# LED_Cube.net
KiCad netlist of a schematic drawn in EAGLE
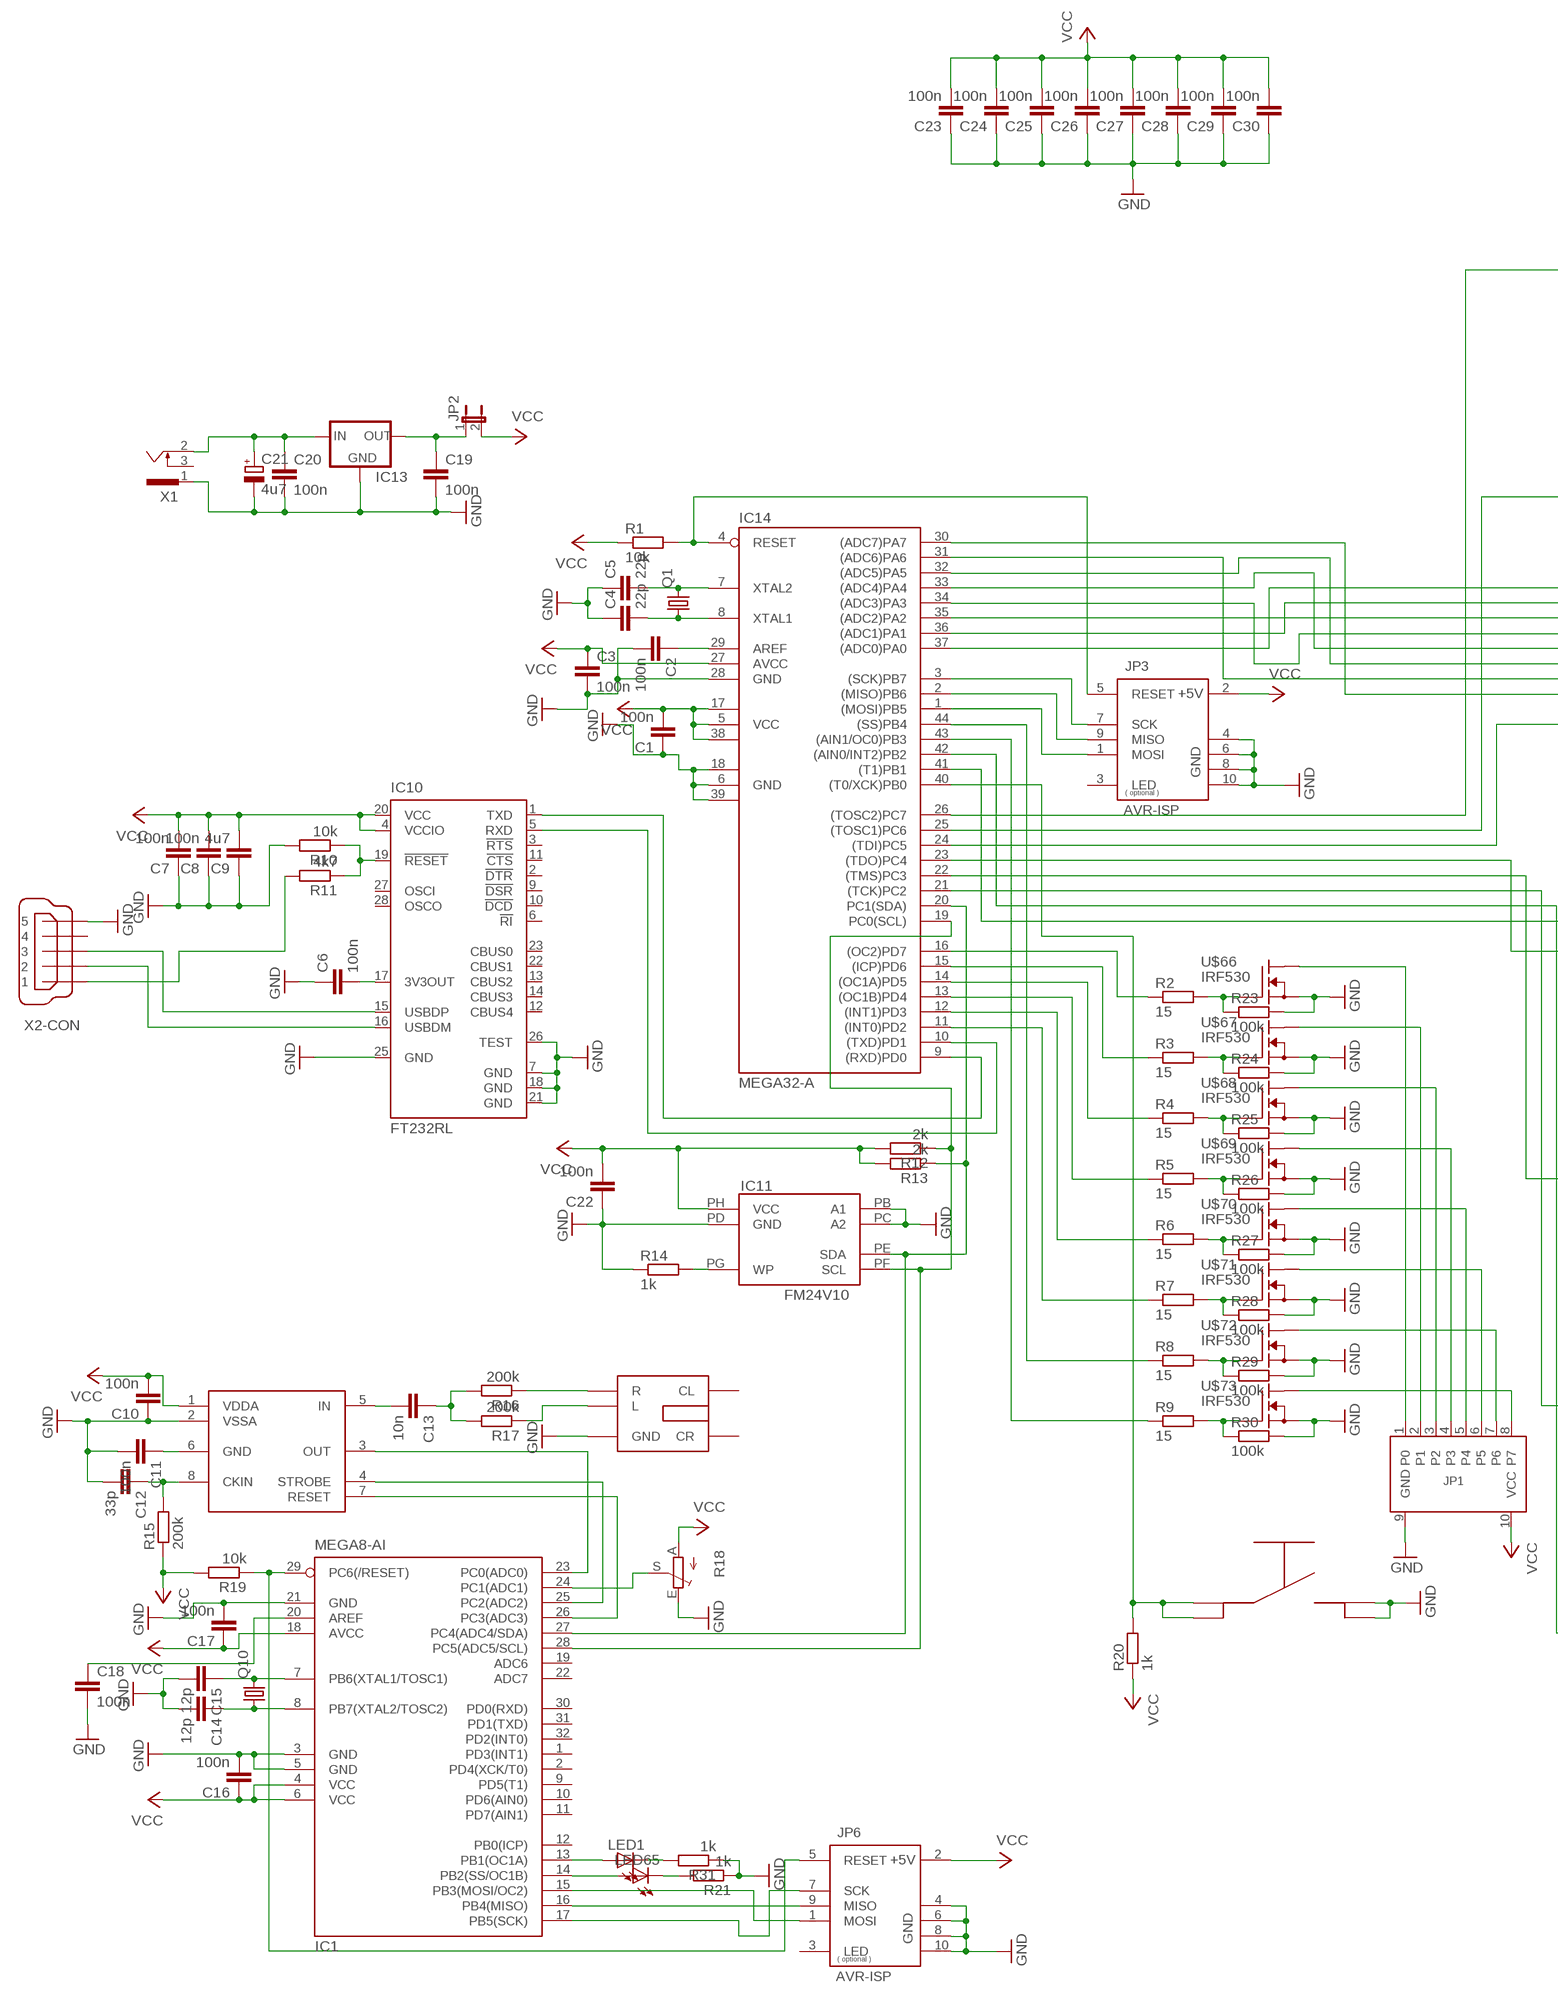
[diagram p0: schematic, sheet 1, part 1 of 2]
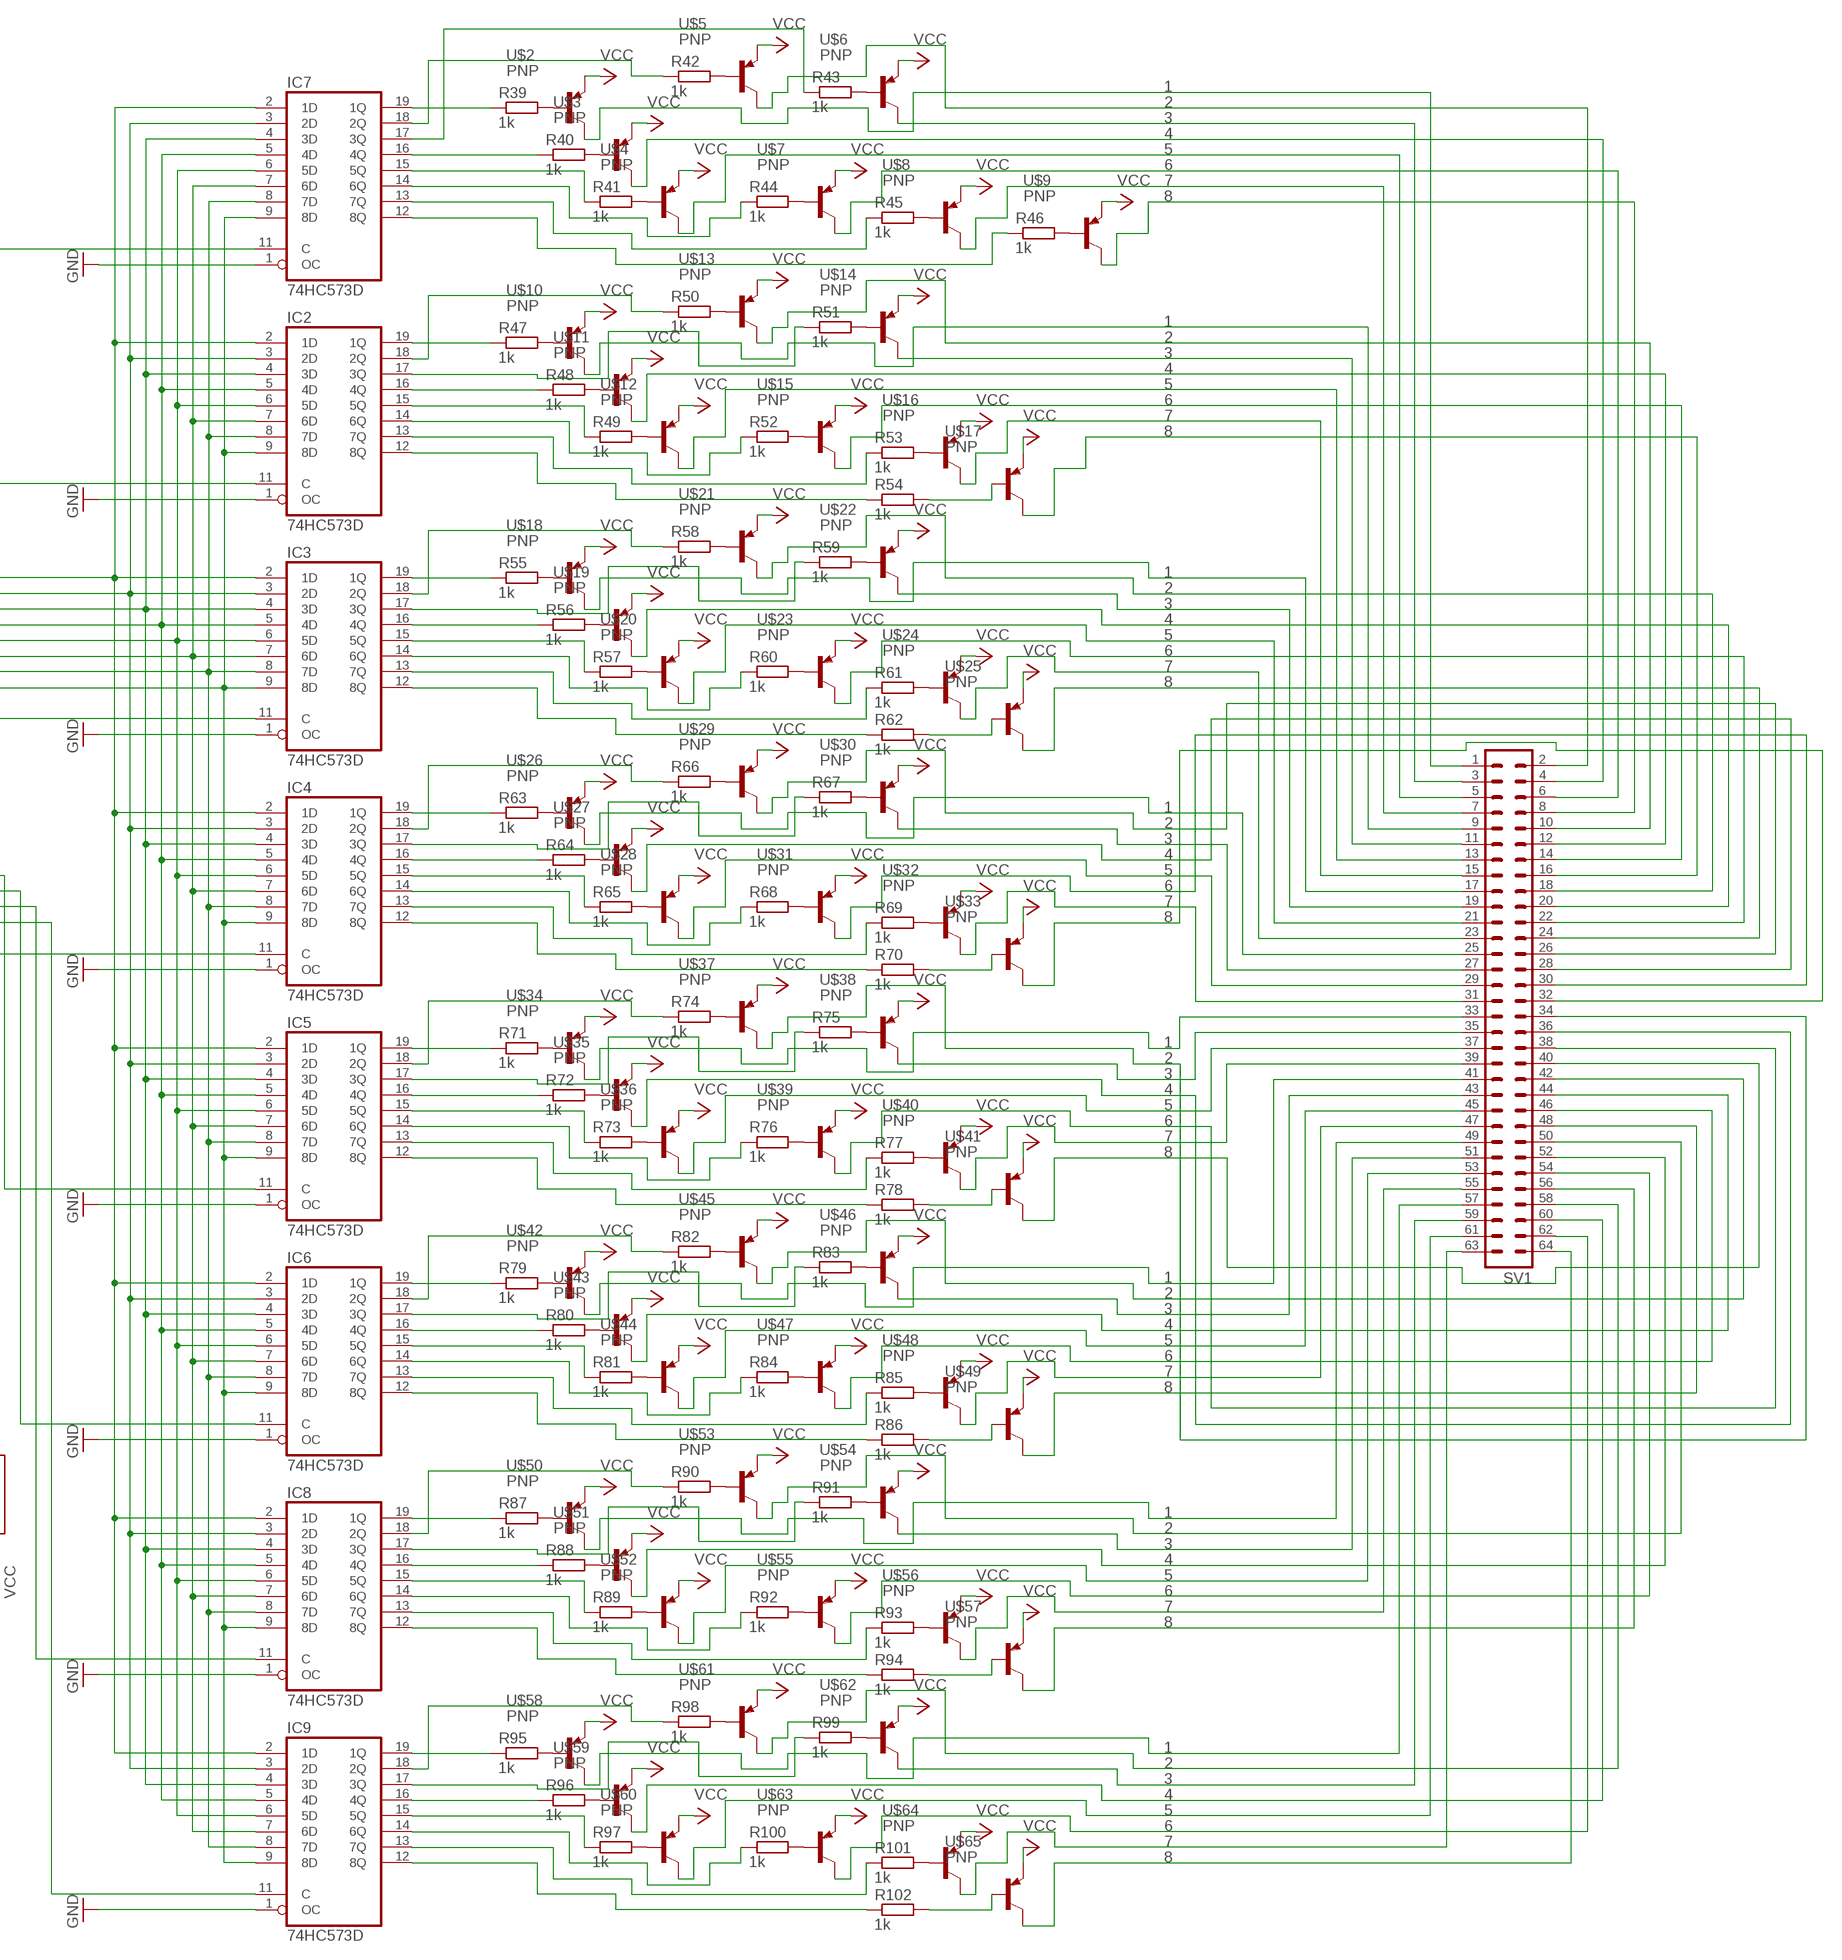
[diagram p1: schematic, sheet 1, part 2 of 2]

(export (version "E")
  (design (tool "Eeschema 10.0.6"))
  (components
    (comp (ref "C1")
      (value "100n")
      (footprint "eagle-import:C0603")
      (libsource (lib "eagle-import") (part "C-EUC0603"))
    )
    (comp (ref "C2")
      (value "100n")
      (footprint "eagle-import:C0603")
      (libsource (lib "eagle-import") (part "C-EUC0603"))
    )
    (comp (ref "C3")
      (value "100n")
      (footprint "eagle-import:C0603")
      (libsource (lib "eagle-import") (part "C-EUC0603"))
    )
    (comp (ref "C4")
      (value "22p")
      (footprint "eagle-import:C0603")
      (libsource (lib "eagle-import") (part "C-EUC0603"))
    )
    (comp (ref "C5")
      (value "22p")
      (footprint "eagle-import:C0603")
      (libsource (lib "eagle-import") (part "C-EUC0603"))
    )
    (comp (ref "C6")
      (value "100n")
      (footprint "eagle-import:C0603")
      (libsource (lib "eagle-import") (part "C-EUC0603"))
    )
    (comp (ref "C7")
      (value "100n")
      (footprint "eagle-import:C0603")
      (libsource (lib "eagle-import") (part "C-EUC0603"))
    )
    (comp (ref "C8")
      (value "100n")
      (footprint "eagle-import:C0603")
      (libsource (lib "eagle-import") (part "C-EUC0603"))
    )
    (comp (ref "C9")
      (value "4u7")
      (footprint "eagle-import:C0603")
      (libsource (lib "eagle-import") (part "C-EUC0603"))
    )
    (comp (ref "C10")
      (value "100n")
      (footprint "eagle-import:C0603")
      (libsource (lib "eagle-import") (part "C-EUC0603"))
    )
    (comp (ref "C11")
      (value "100n")
      (footprint "eagle-import:C0603")
      (libsource (lib "eagle-import") (part "C-EUC0603"))
    )
    (comp (ref "C12")
      (value "33p")
      (footprint "eagle-import:C0603")
      (libsource (lib "eagle-import") (part "C-EUC0603"))
    )
    (comp (ref "C13")
      (value "10n")
      (footprint "eagle-import:C0603")
      (libsource (lib "eagle-import") (part "C-EUC0603"))
    )
    (comp (ref "C14")
      (value "12p")
      (footprint "eagle-import:C0603")
      (libsource (lib "eagle-import") (part "C-EUC0603"))
    )
    (comp (ref "C15")
      (value "12p")
      (footprint "eagle-import:C0603")
      (libsource (lib "eagle-import") (part "C-EUC0603"))
    )
    (comp (ref "C16")
      (value "100n")
      (footprint "eagle-import:C0603")
      (libsource (lib "eagle-import") (part "C-EUC0603"))
    )
    (comp (ref "C17")
      (value "100n")
      (footprint "eagle-import:C0603")
      (libsource (lib "eagle-import") (part "C-EUC0603"))
    )
    (comp (ref "C18")
      (value "100n")
      (footprint "eagle-import:C0603")
      (libsource (lib "eagle-import") (part "C-EUC0603"))
    )
    (comp (ref "C19")
      (value "100n")
      (footprint "eagle-import:C0603")
      (libsource (lib "eagle-import") (part "C-EUC0603"))
    )
    (comp (ref "C20")
      (value "100n")
      (footprint "eagle-import:C0603")
      (libsource (lib "eagle-import") (part "C-EUC0603"))
    )
    (comp (ref "C21")
      (value "4u7")
      (footprint "eagle-import:TAP5-80")
      (libsource (lib "eagle-import") (part "CPOL-EUTAP5-80"))
    )
    (comp (ref "C22")
      (value "100n")
      (footprint "eagle-import:C0603")
      (libsource (lib "eagle-import") (part "C-EUC0603"))
    )
    (comp (ref "C23")
      (value "100n")
      (footprint "eagle-import:C0603")
      (libsource (lib "eagle-import") (part "C-EUC0603"))
    )
    (comp (ref "C24")
      (value "100n")
      (footprint "eagle-import:C0603")
      (libsource (lib "eagle-import") (part "C-EUC0603"))
    )
    (comp (ref "C25")
      (value "100n")
      (footprint "eagle-import:C0603")
      (libsource (lib "eagle-import") (part "C-EUC0603"))
    )
    (comp (ref "C26")
      (value "100n")
      (footprint "eagle-import:C0603")
      (libsource (lib "eagle-import") (part "C-EUC0603"))
    )
    (comp (ref "C27")
      (value "100n")
      (footprint "eagle-import:C0603")
      (libsource (lib "eagle-import") (part "C-EUC0603"))
    )
    (comp (ref "C28")
      (value "100n")
      (footprint "eagle-import:C0603")
      (libsource (lib "eagle-import") (part "C-EUC0603"))
    )
    (comp (ref "C29")
      (value "100n")
      (footprint "eagle-import:C0603")
      (libsource (lib "eagle-import") (part "C-EUC0603"))
    )
    (comp (ref "C30")
      (value "100n")
      (footprint "eagle-import:C0603")
      (libsource (lib "eagle-import") (part "C-EUC0603"))
    )
    (comp (ref "IC1")
      (value "MEGA8-AI")
      (footprint "eagle-import:TQFP32-08")
      (fields (field (name "MPN") "ATMEGA8-16AU"))
      (libsource (lib "eagle-import") (part "MEGA8-AI"))
    )
    (comp (ref "IC2")
      (value "74HC573D")
      (footprint "eagle-import:SO20W")
      (libsource (lib "eagle-import") (part "74573DHC"))
    )
    (comp (ref "IC3")
      (value "74HC573D")
      (footprint "eagle-import:SO20W")
      (libsource (lib "eagle-import") (part "74573DHC"))
    )
    (comp (ref "IC4")
      (value "74HC573D")
      (footprint "eagle-import:SO20W")
      (libsource (lib "eagle-import") (part "74573DHC"))
    )
    (comp (ref "IC5")
      (value "74HC573D")
      (footprint "eagle-import:SO20W")
      (libsource (lib "eagle-import") (part "74573DHC"))
    )
    (comp (ref "IC6")
      (value "74HC573D")
      (footprint "eagle-import:SO20W")
      (libsource (lib "eagle-import") (part "74573DHC"))
    )
    (comp (ref "IC7")
      (value "74HC573D")
      (footprint "eagle-import:SO20W")
      (libsource (lib "eagle-import") (part "74573DHC"))
    )
    (comp (ref "IC8")
      (value "74HC573D")
      (footprint "eagle-import:SO20W")
      (libsource (lib "eagle-import") (part "74573DHC"))
    )
    (comp (ref "IC9")
      (value "74HC573D")
      (footprint "eagle-import:SO20W")
      (libsource (lib "eagle-import") (part "74573DHC"))
    )
    (comp (ref "IC10")
      (value "FT232RL")
      (footprint "eagle-import:SSOP28")
      (libsource (lib "eagle-import") (part "FT232RL"))
    )
    (comp (ref "IC11")
      (value "FM24V10")
      (footprint "eagle-import:SOIC8")
      (libsource (lib "eagle-import") (part "FM24V10"))
    )
    (comp (ref "IC12")
      (value "MSGEQ7")
      (footprint "eagle-import:DIP8")
      (libsource (lib "eagle-import") (part "MSGEQ7"))
    )
    (comp (ref "IC13")
      (value "78XXS")
      (footprint "eagle-import:78XXS")
      (libsource (lib "eagle-import") (part "78XXS"))
    )
    (comp (ref "IC14")
      (value "MEGA32-A")
      (footprint "eagle-import:TQFP44")
      (fields (field (name "MPN") "ATMEGA32-16AU"))
      (libsource (lib "eagle-import") (part "MEGA32-A"))
    )
    (comp (ref "JP1")
      (value "PORT")
      (footprint "eagle-import:ML10")
      (libsource (lib "eagle-import") (part "PORT"))
    )
    (comp (ref "JP2")
      (value "JP1E")
      (footprint "eagle-import:JP1")
      (libsource (lib "eagle-import") (part "JP1E"))
    )
    (comp (ref "JP3")
      (value "AVR-ISP")
      (footprint "eagle-import:ML10")
      (libsource (lib "eagle-import") (part "AVR-ISP"))
    )
    (comp (ref "JP6")
      (value "AVR-ISP")
      (footprint "eagle-import:ML10")
      (libsource (lib "eagle-import") (part "AVR-ISP"))
    )
    (comp (ref "LED1")
      (value "LEDCHIPLED_0603")
      (footprint "eagle-import:CHIPLED_0603")
      (libsource (lib "eagle-import") (part "LEDCHIPLED_0603"))
    )
    (comp (ref "LED65")
      (value "LEDCHIPLED_0603")
      (footprint "eagle-import:CHIPLED_0603")
      (libsource (lib "eagle-import") (part "LEDCHIPLED_0603"))
    )
    (comp (ref "Q1")
      (value "CRYSTALHC49S")
      (footprint "eagle-import:HC49_S")
      (libsource (lib "eagle-import") (part "CRYSTALHC49S"))
    )
    (comp (ref "Q10")
      (value "CRYSTALHC49S")
      (footprint "eagle-import:HC49_S")
      (libsource (lib "eagle-import") (part "CRYSTALHC49S"))
    )
    (comp (ref "R1")
      (value "10k")
      (footprint "eagle-import:R0603")
      (libsource (lib "eagle-import") (part "R-EU_R0603"))
    )
    (comp (ref "R2")
      (value "15")
      (footprint "eagle-import:R0603")
      (libsource (lib "eagle-import") (part "R-EU_R0603"))
    )
    (comp (ref "R3")
      (value "15")
      (footprint "eagle-import:R0603")
      (libsource (lib "eagle-import") (part "R-EU_R0603"))
    )
    (comp (ref "R4")
      (value "15")
      (footprint "eagle-import:R0603")
      (libsource (lib "eagle-import") (part "R-EU_R0603"))
    )
    (comp (ref "R5")
      (value "15")
      (footprint "eagle-import:R0603")
      (libsource (lib "eagle-import") (part "R-EU_R0603"))
    )
    (comp (ref "R6")
      (value "15")
      (footprint "eagle-import:R0603")
      (libsource (lib "eagle-import") (part "R-EU_R0603"))
    )
    (comp (ref "R7")
      (value "15")
      (footprint "eagle-import:R0603")
      (libsource (lib "eagle-import") (part "R-EU_R0603"))
    )
    (comp (ref "R8")
      (value "15")
      (footprint "eagle-import:R0603")
      (libsource (lib "eagle-import") (part "R-EU_R0603"))
    )
    (comp (ref "R9")
      (value "15")
      (footprint "eagle-import:R0603")
      (libsource (lib "eagle-import") (part "R-EU_R0603"))
    )
    (comp (ref "R10")
      (value "10k")
      (footprint "eagle-import:R0603")
      (libsource (lib "eagle-import") (part "R-EU_R0603"))
    )
    (comp (ref "R11")
      (value "4k7")
      (footprint "eagle-import:R0603")
      (libsource (lib "eagle-import") (part "R-EU_R0603"))
    )
    (comp (ref "R12")
      (value "2k")
      (footprint "eagle-import:R0603")
      (libsource (lib "eagle-import") (part "R-EU_R0603"))
    )
    (comp (ref "R13")
      (value "2k")
      (footprint "eagle-import:R0603")
      (libsource (lib "eagle-import") (part "R-EU_R0603"))
    )
    (comp (ref "R14")
      (value "1k")
      (footprint "eagle-import:R0603")
      (libsource (lib "eagle-import") (part "R-EU_R0603"))
    )
    (comp (ref "R15")
      (value "200k")
      (footprint "eagle-import:R0603")
      (libsource (lib "eagle-import") (part "R-EU_R0603"))
    )
    (comp (ref "R16")
      (value "200k")
      (footprint "eagle-import:R0603")
      (libsource (lib "eagle-import") (part "R-EU_R0603"))
    )
    (comp (ref "R17")
      (value "200k")
      (footprint "eagle-import:R0603")
      (libsource (lib "eagle-import") (part "R-EU_R0603"))
    )
    (comp (ref "R18")
      (value "TRIM_EU-PT10S")
      (footprint "eagle-import:PT-10S")
      (libsource (lib "eagle-import") (part "TRIM_EU-PT10S"))
    )
    (comp (ref "R19")
      (value "10k")
      (footprint "eagle-import:R0603")
      (libsource (lib "eagle-import") (part "R-EU_R0603"))
    )
    (comp (ref "R20")
      (value "1k")
      (footprint "eagle-import:R0603")
      (libsource (lib "eagle-import") (part "R-EU_R0603"))
    )
    (comp (ref "R21")
      (value "1k")
      (footprint "eagle-import:R0603")
      (libsource (lib "eagle-import") (part "R-EU_R0603"))
    )
    (comp (ref "R23")
      (value "100k")
      (footprint "eagle-import:R0603")
      (libsource (lib "eagle-import") (part "R-EU_R0603"))
    )
    (comp (ref "R24")
      (value "100k")
      (footprint "eagle-import:R0603")
      (libsource (lib "eagle-import") (part "R-EU_R0603"))
    )
    (comp (ref "R25")
      (value "100k")
      (footprint "eagle-import:R0603")
      (libsource (lib "eagle-import") (part "R-EU_R0603"))
    )
    (comp (ref "R26")
      (value "100k")
      (footprint "eagle-import:R0603")
      (libsource (lib "eagle-import") (part "R-EU_R0603"))
    )
    (comp (ref "R27")
      (value "100k")
      (footprint "eagle-import:R0603")
      (libsource (lib "eagle-import") (part "R-EU_R0603"))
    )
    (comp (ref "R28")
      (value "100k")
      (footprint "eagle-import:R0603")
      (libsource (lib "eagle-import") (part "R-EU_R0603"))
    )
    (comp (ref "R29")
      (value "100k")
      (footprint "eagle-import:R0603")
      (libsource (lib "eagle-import") (part "R-EU_R0603"))
    )
    (comp (ref "R30")
      (value "100k")
      (footprint "eagle-import:R0603")
      (libsource (lib "eagle-import") (part "R-EU_R0603"))
    )
    (comp (ref "R31")
      (value "1k")
      (footprint "eagle-import:R0603")
      (libsource (lib "eagle-import") (part "R-EU_R0603"))
    )
    (comp (ref "R39")
      (value "1k")
      (footprint "eagle-import:R0603")
      (libsource (lib "eagle-import") (part "R-EU_R0603"))
    )
    (comp (ref "R40")
      (value "1k")
      (footprint "eagle-import:R0603")
      (libsource (lib "eagle-import") (part "R-EU_R0603"))
    )
    (comp (ref "R41")
      (value "1k")
      (footprint "eagle-import:R0603")
      (libsource (lib "eagle-import") (part "R-EU_R0603"))
    )
    (comp (ref "R42")
      (value "1k")
      (footprint "eagle-import:R0603")
      (libsource (lib "eagle-import") (part "R-EU_R0603"))
    )
    (comp (ref "R43")
      (value "1k")
      (footprint "eagle-import:R0603")
      (libsource (lib "eagle-import") (part "R-EU_R0603"))
    )
    (comp (ref "R44")
      (value "1k")
      (footprint "eagle-import:R0603")
      (libsource (lib "eagle-import") (part "R-EU_R0603"))
    )
    (comp (ref "R45")
      (value "1k")
      (footprint "eagle-import:R0603")
      (libsource (lib "eagle-import") (part "R-EU_R0603"))
    )
    (comp (ref "R46")
      (value "1k")
      (footprint "eagle-import:R0603")
      (libsource (lib "eagle-import") (part "R-EU_R0603"))
    )
    (comp (ref "R47")
      (value "1k")
      (footprint "eagle-import:R0603")
      (libsource (lib "eagle-import") (part "R-EU_R0603"))
    )
    (comp (ref "R48")
      (value "1k")
      (footprint "eagle-import:R0603")
      (libsource (lib "eagle-import") (part "R-EU_R0603"))
    )
    (comp (ref "R49")
      (value "1k")
      (footprint "eagle-import:R0603")
      (libsource (lib "eagle-import") (part "R-EU_R0603"))
    )
    (comp (ref "R50")
      (value "1k")
      (footprint "eagle-import:R0603")
      (libsource (lib "eagle-import") (part "R-EU_R0603"))
    )
    (comp (ref "R51")
      (value "1k")
      (footprint "eagle-import:R0603")
      (libsource (lib "eagle-import") (part "R-EU_R0603"))
    )
    (comp (ref "R52")
      (value "1k")
      (footprint "eagle-import:R0603")
      (libsource (lib "eagle-import") (part "R-EU_R0603"))
    )
    (comp (ref "R53")
      (value "1k")
      (footprint "eagle-import:R0603")
      (libsource (lib "eagle-import") (part "R-EU_R0603"))
    )
    (comp (ref "R54")
      (value "1k")
      (footprint "eagle-import:R0603")
      (libsource (lib "eagle-import") (part "R-EU_R0603"))
    )
    (comp (ref "R55")
      (value "1k")
      (footprint "eagle-import:R0603")
      (libsource (lib "eagle-import") (part "R-EU_R0603"))
    )
    (comp (ref "R56")
      (value "1k")
      (footprint "eagle-import:R0603")
      (libsource (lib "eagle-import") (part "R-EU_R0603"))
    )
    (comp (ref "R57")
      (value "1k")
      (footprint "eagle-import:R0603")
      (libsource (lib "eagle-import") (part "R-EU_R0603"))
    )
    (comp (ref "R58")
      (value "1k")
      (footprint "eagle-import:R0603")
      (libsource (lib "eagle-import") (part "R-EU_R0603"))
    )
    (comp (ref "R59")
      (value "1k")
      (footprint "eagle-import:R0603")
      (libsource (lib "eagle-import") (part "R-EU_R0603"))
    )
    (comp (ref "R60")
      (value "1k")
      (footprint "eagle-import:R0603")
      (libsource (lib "eagle-import") (part "R-EU_R0603"))
    )
    (comp (ref "R61")
      (value "1k")
      (footprint "eagle-import:R0603")
      (libsource (lib "eagle-import") (part "R-EU_R0603"))
    )
    (comp (ref "R62")
      (value "1k")
      (footprint "eagle-import:R0603")
      (libsource (lib "eagle-import") (part "R-EU_R0603"))
    )
    (comp (ref "R63")
      (value "1k")
      (footprint "eagle-import:R0603")
      (libsource (lib "eagle-import") (part "R-EU_R0603"))
    )
    (comp (ref "R64")
      (value "1k")
      (footprint "eagle-import:R0603")
      (libsource (lib "eagle-import") (part "R-EU_R0603"))
    )
    (comp (ref "R65")
      (value "1k")
      (footprint "eagle-import:R0603")
      (libsource (lib "eagle-import") (part "R-EU_R0603"))
    )
    (comp (ref "R66")
      (value "1k")
      (footprint "eagle-import:R0603")
      (libsource (lib "eagle-import") (part "R-EU_R0603"))
    )
    (comp (ref "R67")
      (value "1k")
      (footprint "eagle-import:R0603")
      (libsource (lib "eagle-import") (part "R-EU_R0603"))
    )
    (comp (ref "R68")
      (value "1k")
      (footprint "eagle-import:R0603")
      (libsource (lib "eagle-import") (part "R-EU_R0603"))
    )
    (comp (ref "R69")
      (value "1k")
      (footprint "eagle-import:R0603")
      (libsource (lib "eagle-import") (part "R-EU_R0603"))
    )
    (comp (ref "R70")
      (value "1k")
      (footprint "eagle-import:R0603")
      (libsource (lib "eagle-import") (part "R-EU_R0603"))
    )
    (comp (ref "R71")
      (value "1k")
      (footprint "eagle-import:R0603")
      (libsource (lib "eagle-import") (part "R-EU_R0603"))
    )
    (comp (ref "R72")
      (value "1k")
      (footprint "eagle-import:R0603")
      (libsource (lib "eagle-import") (part "R-EU_R0603"))
    )
    (comp (ref "R73")
      (value "1k")
      (footprint "eagle-import:R0603")
      (libsource (lib "eagle-import") (part "R-EU_R0603"))
    )
    (comp (ref "R74")
      (value "1k")
      (footprint "eagle-import:R0603")
      (libsource (lib "eagle-import") (part "R-EU_R0603"))
    )
    (comp (ref "R75")
      (value "1k")
      (footprint "eagle-import:R0603")
      (libsource (lib "eagle-import") (part "R-EU_R0603"))
    )
    (comp (ref "R76")
      (value "1k")
      (footprint "eagle-import:R0603")
      (libsource (lib "eagle-import") (part "R-EU_R0603"))
    )
    (comp (ref "R77")
      (value "1k")
      (footprint "eagle-import:R0603")
      (libsource (lib "eagle-import") (part "R-EU_R0603"))
    )
    (comp (ref "R78")
      (value "1k")
      (footprint "eagle-import:R0603")
      (libsource (lib "eagle-import") (part "R-EU_R0603"))
    )
    (comp (ref "R79")
      (value "1k")
      (footprint "eagle-import:R0603")
      (libsource (lib "eagle-import") (part "R-EU_R0603"))
    )
    (comp (ref "R80")
      (value "1k")
      (footprint "eagle-import:R0603")
      (libsource (lib "eagle-import") (part "R-EU_R0603"))
    )
    (comp (ref "R81")
      (value "1k")
      (footprint "eagle-import:R0603")
      (libsource (lib "eagle-import") (part "R-EU_R0603"))
    )
    (comp (ref "R82")
      (value "1k")
      (footprint "eagle-import:R0603")
      (libsource (lib "eagle-import") (part "R-EU_R0603"))
    )
    (comp (ref "R83")
      (value "1k")
      (footprint "eagle-import:R0603")
      (libsource (lib "eagle-import") (part "R-EU_R0603"))
    )
    (comp (ref "R84")
      (value "1k")
      (footprint "eagle-import:R0603")
      (libsource (lib "eagle-import") (part "R-EU_R0603"))
    )
    (comp (ref "R85")
      (value "1k")
      (footprint "eagle-import:R0603")
      (libsource (lib "eagle-import") (part "R-EU_R0603"))
    )
    (comp (ref "R86")
      (value "1k")
      (footprint "eagle-import:R0603")
      (libsource (lib "eagle-import") (part "R-EU_R0603"))
    )
    (comp (ref "R87")
      (value "1k")
      (footprint "eagle-import:R0603")
      (libsource (lib "eagle-import") (part "R-EU_R0603"))
    )
    (comp (ref "R88")
      (value "1k")
      (footprint "eagle-import:R0603")
      (libsource (lib "eagle-import") (part "R-EU_R0603"))
    )
    (comp (ref "R89")
      (value "1k")
      (footprint "eagle-import:R0603")
      (libsource (lib "eagle-import") (part "R-EU_R0603"))
    )
    (comp (ref "R90")
      (value "1k")
      (footprint "eagle-import:R0603")
      (libsource (lib "eagle-import") (part "R-EU_R0603"))
    )
    (comp (ref "R91")
      (value "1k")
      (footprint "eagle-import:R0603")
      (libsource (lib "eagle-import") (part "R-EU_R0603"))
    )
    (comp (ref "R92")
      (value "1k")
      (footprint "eagle-import:R0603")
      (libsource (lib "eagle-import") (part "R-EU_R0603"))
    )
    (comp (ref "R93")
      (value "1k")
      (footprint "eagle-import:R0603")
      (libsource (lib "eagle-import") (part "R-EU_R0603"))
    )
    (comp (ref "R94")
      (value "1k")
      (footprint "eagle-import:R0603")
      (libsource (lib "eagle-import") (part "R-EU_R0603"))
    )
    (comp (ref "R95")
      (value "1k")
      (footprint "eagle-import:R0603")
      (libsource (lib "eagle-import") (part "R-EU_R0603"))
    )
    (comp (ref "R96")
      (value "1k")
      (footprint "eagle-import:R0603")
      (libsource (lib "eagle-import") (part "R-EU_R0603"))
    )
    (comp (ref "R97")
      (value "1k")
      (footprint "eagle-import:R0603")
      (libsource (lib "eagle-import") (part "R-EU_R0603"))
    )
    (comp (ref "R98")
      (value "1k")
      (footprint "eagle-import:R0603")
      (libsource (lib "eagle-import") (part "R-EU_R0603"))
    )
    (comp (ref "R99")
      (value "1k")
      (footprint "eagle-import:R0603")
      (libsource (lib "eagle-import") (part "R-EU_R0603"))
    )
    (comp (ref "R100")
      (value "1k")
      (footprint "eagle-import:R0603")
      (libsource (lib "eagle-import") (part "R-EU_R0603"))
    )
    (comp (ref "R101")
      (value "1k")
      (footprint "eagle-import:R0603")
      (libsource (lib "eagle-import") (part "R-EU_R0603"))
    )
    (comp (ref "R102")
      (value "1k")
      (footprint "eagle-import:R0603")
      (libsource (lib "eagle-import") (part "R-EU_R0603"))
    )
    (comp (ref "SV1")
      (value "ML64")
      (footprint "eagle-import:ML64")
      (libsource (lib "eagle-import") (part "ML64"))
    )
    (comp (ref "U$1")
      (value "KLINKENBUCHSE")
      (footprint "eagle-import:KLINKEPRINT")
      (libsource (lib "eagle-import") (part "KLINKENBUCHSE"))
    )
    (comp (ref "U$2")
      (value "PNP")
      (footprint "eagle-import:SOT323")
      (libsource (lib "eagle-import") (part "PNP"))
    )
    (comp (ref "U$3")
      (value "PNP")
      (footprint "eagle-import:SOT323")
      (libsource (lib "eagle-import") (part "PNP"))
    )
    (comp (ref "U$4")
      (value "PNP")
      (footprint "eagle-import:SOT323")
      (libsource (lib "eagle-import") (part "PNP"))
    )
    (comp (ref "U$5")
      (value "PNP")
      (footprint "eagle-import:SOT323")
      (libsource (lib "eagle-import") (part "PNP"))
    )
    (comp (ref "U$6")
      (value "PNP")
      (footprint "eagle-import:SOT323")
      (libsource (lib "eagle-import") (part "PNP"))
    )
    (comp (ref "U$7")
      (value "PNP")
      (footprint "eagle-import:SOT323")
      (libsource (lib "eagle-import") (part "PNP"))
    )
    (comp (ref "U$8")
      (value "PNP")
      (footprint "eagle-import:SOT323")
      (libsource (lib "eagle-import") (part "PNP"))
    )
    (comp (ref "U$9")
      (value "PNP")
      (footprint "eagle-import:SOT323")
      (libsource (lib "eagle-import") (part "PNP"))
    )
    (comp (ref "U$10")
      (value "PNP")
      (footprint "eagle-import:SOT323")
      (libsource (lib "eagle-import") (part "PNP"))
    )
    (comp (ref "U$11")
      (value "PNP")
      (footprint "eagle-import:SOT323")
      (libsource (lib "eagle-import") (part "PNP"))
    )
    (comp (ref "U$12")
      (value "PNP")
      (footprint "eagle-import:SOT323")
      (libsource (lib "eagle-import") (part "PNP"))
    )
    (comp (ref "U$13")
      (value "PNP")
      (footprint "eagle-import:SOT323")
      (libsource (lib "eagle-import") (part "PNP"))
    )
    (comp (ref "U$14")
      (value "PNP")
      (footprint "eagle-import:SOT323")
      (libsource (lib "eagle-import") (part "PNP"))
    )
    (comp (ref "U$15")
      (value "PNP")
      (footprint "eagle-import:SOT323")
      (libsource (lib "eagle-import") (part "PNP"))
    )
    (comp (ref "U$16")
      (value "PNP")
      (footprint "eagle-import:SOT323")
      (libsource (lib "eagle-import") (part "PNP"))
    )
    (comp (ref "U$17")
      (value "PNP")
      (footprint "eagle-import:SOT323")
      (libsource (lib "eagle-import") (part "PNP"))
    )
    (comp (ref "U$18")
      (value "PNP")
      (footprint "eagle-import:SOT323")
      (libsource (lib "eagle-import") (part "PNP"))
    )
    (comp (ref "U$19")
      (value "PNP")
      (footprint "eagle-import:SOT323")
      (libsource (lib "eagle-import") (part "PNP"))
    )
    (comp (ref "U$20")
      (value "PNP")
      (footprint "eagle-import:SOT323")
      (libsource (lib "eagle-import") (part "PNP"))
    )
    (comp (ref "U$21")
      (value "PNP")
      (footprint "eagle-import:SOT323")
      (libsource (lib "eagle-import") (part "PNP"))
    )
    (comp (ref "U$22")
      (value "PNP")
      (footprint "eagle-import:SOT323")
      (libsource (lib "eagle-import") (part "PNP"))
    )
    (comp (ref "U$23")
      (value "PNP")
      (footprint "eagle-import:SOT323")
      (libsource (lib "eagle-import") (part "PNP"))
    )
    (comp (ref "U$24")
      (value "PNP")
      (footprint "eagle-import:SOT323")
      (libsource (lib "eagle-import") (part "PNP"))
    )
    (comp (ref "U$25")
      (value "PNP")
      (footprint "eagle-import:SOT323")
      (libsource (lib "eagle-import") (part "PNP"))
    )
    (comp (ref "U$26")
      (value "PNP")
      (footprint "eagle-import:SOT323")
      (libsource (lib "eagle-import") (part "PNP"))
    )
    (comp (ref "U$27")
      (value "PNP")
      (footprint "eagle-import:SOT323")
      (libsource (lib "eagle-import") (part "PNP"))
    )
    (comp (ref "U$28")
      (value "PNP")
      (footprint "eagle-import:SOT323")
      (libsource (lib "eagle-import") (part "PNP"))
    )
    (comp (ref "U$29")
      (value "PNP")
      (footprint "eagle-import:SOT323")
      (libsource (lib "eagle-import") (part "PNP"))
    )
    (comp (ref "U$30")
      (value "PNP")
      (footprint "eagle-import:SOT323")
      (libsource (lib "eagle-import") (part "PNP"))
    )
    (comp (ref "U$31")
      (value "PNP")
      (footprint "eagle-import:SOT323")
      (libsource (lib "eagle-import") (part "PNP"))
    )
    (comp (ref "U$32")
      (value "PNP")
      (footprint "eagle-import:SOT323")
      (libsource (lib "eagle-import") (part "PNP"))
    )
    (comp (ref "U$33")
      (value "PNP")
      (footprint "eagle-import:SOT323")
      (libsource (lib "eagle-import") (part "PNP"))
    )
    (comp (ref "U$34")
      (value "PNP")
      (footprint "eagle-import:SOT323")
      (libsource (lib "eagle-import") (part "PNP"))
    )
    (comp (ref "U$35")
      (value "PNP")
      (footprint "eagle-import:SOT323")
      (libsource (lib "eagle-import") (part "PNP"))
    )
    (comp (ref "U$36")
      (value "PNP")
      (footprint "eagle-import:SOT323")
      (libsource (lib "eagle-import") (part "PNP"))
    )
    (comp (ref "U$37")
      (value "PNP")
      (footprint "eagle-import:SOT323")
      (libsource (lib "eagle-import") (part "PNP"))
    )
    (comp (ref "U$38")
      (value "PNP")
      (footprint "eagle-import:SOT323")
      (libsource (lib "eagle-import") (part "PNP"))
    )
    (comp (ref "U$39")
      (value "PNP")
      (footprint "eagle-import:SOT323")
      (libsource (lib "eagle-import") (part "PNP"))
    )
    (comp (ref "U$40")
      (value "PNP")
      (footprint "eagle-import:SOT323")
      (libsource (lib "eagle-import") (part "PNP"))
    )
    (comp (ref "U$41")
      (value "PNP")
      (footprint "eagle-import:SOT323")
      (libsource (lib "eagle-import") (part "PNP"))
    )
    (comp (ref "U$42")
      (value "PNP")
      (footprint "eagle-import:SOT323")
      (libsource (lib "eagle-import") (part "PNP"))
    )
    (comp (ref "U$43")
      (value "PNP")
      (footprint "eagle-import:SOT323")
      (libsource (lib "eagle-import") (part "PNP"))
    )
    (comp (ref "U$44")
      (value "PNP")
      (footprint "eagle-import:SOT323")
      (libsource (lib "eagle-import") (part "PNP"))
    )
    (comp (ref "U$45")
      (value "PNP")
      (footprint "eagle-import:SOT323")
      (libsource (lib "eagle-import") (part "PNP"))
    )
    (comp (ref "U$46")
      (value "PNP")
      (footprint "eagle-import:SOT323")
      (libsource (lib "eagle-import") (part "PNP"))
    )
    (comp (ref "U$47")
      (value "PNP")
      (footprint "eagle-import:SOT323")
      (libsource (lib "eagle-import") (part "PNP"))
    )
    (comp (ref "U$48")
      (value "PNP")
      (footprint "eagle-import:SOT323")
      (libsource (lib "eagle-import") (part "PNP"))
    )
    (comp (ref "U$49")
      (value "PNP")
      (footprint "eagle-import:SOT323")
      (libsource (lib "eagle-import") (part "PNP"))
    )
    (comp (ref "U$50")
      (value "PNP")
      (footprint "eagle-import:SOT323")
      (libsource (lib "eagle-import") (part "PNP"))
    )
    (comp (ref "U$51")
      (value "PNP")
      (footprint "eagle-import:SOT323")
      (libsource (lib "eagle-import") (part "PNP"))
    )
    (comp (ref "U$52")
      (value "PNP")
      (footprint "eagle-import:SOT323")
      (libsource (lib "eagle-import") (part "PNP"))
    )
    (comp (ref "U$53")
      (value "PNP")
      (footprint "eagle-import:SOT323")
      (libsource (lib "eagle-import") (part "PNP"))
    )
    (comp (ref "U$54")
      (value "PNP")
      (footprint "eagle-import:SOT323")
      (libsource (lib "eagle-import") (part "PNP"))
    )
    (comp (ref "U$55")
      (value "PNP")
      (footprint "eagle-import:SOT323")
      (libsource (lib "eagle-import") (part "PNP"))
    )
    (comp (ref "U$56")
      (value "PNP")
      (footprint "eagle-import:SOT323")
      (libsource (lib "eagle-import") (part "PNP"))
    )
    (comp (ref "U$57")
      (value "PNP")
      (footprint "eagle-import:SOT323")
      (libsource (lib "eagle-import") (part "PNP"))
    )
    (comp (ref "U$58")
      (value "PNP")
      (footprint "eagle-import:SOT323")
      (libsource (lib "eagle-import") (part "PNP"))
    )
    (comp (ref "U$59")
      (value "PNP")
      (footprint "eagle-import:SOT323")
      (libsource (lib "eagle-import") (part "PNP"))
    )
    (comp (ref "U$60")
      (value "PNP")
      (footprint "eagle-import:SOT323")
      (libsource (lib "eagle-import") (part "PNP"))
    )
    (comp (ref "U$61")
      (value "PNP")
      (footprint "eagle-import:SOT323")
      (libsource (lib "eagle-import") (part "PNP"))
    )
    (comp (ref "U$62")
      (value "PNP")
      (footprint "eagle-import:SOT323")
      (libsource (lib "eagle-import") (part "PNP"))
    )
    (comp (ref "U$63")
      (value "PNP")
      (footprint "eagle-import:SOT323")
      (libsource (lib "eagle-import") (part "PNP"))
    )
    (comp (ref "U$64")
      (value "PNP")
      (footprint "eagle-import:SOT323")
      (libsource (lib "eagle-import") (part "PNP"))
    )
    (comp (ref "U$65")
      (value "PNP")
      (footprint "eagle-import:SOT323")
      (libsource (lib "eagle-import") (part "PNP"))
    )
    (comp (ref "U$66")
      (value "IRF530")
      (footprint "eagle-import:TO220-3V")
      (libsource (lib "eagle-import") (part "IRF530"))
    )
    (comp (ref "U$67")
      (value "IRF530")
      (footprint "eagle-import:TO220-3V")
      (libsource (lib "eagle-import") (part "IRF530"))
    )
    (comp (ref "U$68")
      (value "IRF530")
      (footprint "eagle-import:TO220-3V")
      (libsource (lib "eagle-import") (part "IRF530"))
    )
    (comp (ref "U$69")
      (value "IRF530")
      (footprint "eagle-import:TO220-3V")
      (libsource (lib "eagle-import") (part "IRF530"))
    )
    (comp (ref "U$70")
      (value "IRF530")
      (footprint "eagle-import:TO220-3V")
      (libsource (lib "eagle-import") (part "IRF530"))
    )
    (comp (ref "U$71")
      (value "IRF530")
      (footprint "eagle-import:TO220-3V")
      (libsource (lib "eagle-import") (part "IRF530"))
    )
    (comp (ref "U$72")
      (value "IRF530")
      (footprint "eagle-import:TO220-3V")
      (libsource (lib "eagle-import") (part "IRF530"))
    )
    (comp (ref "U$73")
      (value "IRF530")
      (footprint "eagle-import:TO220-3V")
      (libsource (lib "eagle-import") (part "IRF530"))
    )
    (comp (ref "U$74")
      (value "TASTER")
      (footprint "eagle-import:SMDTASTER")
      (libsource (lib "eagle-import") (part "TASTER"))
    )
    (comp (ref "X1")
      (value "733980-62")
      (footprint "eagle-import:733980-62")
      (libsource (lib "eagle-import") (part "73398?0-62"))
    )
    (comp (ref "X2")
      (value "USB-B-MINI-SMD")
      (footprint "eagle-import:USB-B-MINI-SMD")
      (libsource (lib "eagle-import") (part "USB-B-MINI-SMD"))
    )
  )
  (nets
    (net (code "1") (name "GND") (class "Default")
      (node (ref "C1") (pin "1") (pinfunction "1_1") (pintype "passive"))
      (node (ref "C10") (pin "1") (pinfunction "1_1") (pintype "passive"))
      (node (ref "C11") (pin "2") (pinfunction "2_2") (pintype "passive"))
      (node (ref "C12") (pin "2") (pinfunction "2_2") (pintype "passive"))
      (node (ref "C14") (pin "2") (pinfunction "2_2") (pintype "passive"))
      (node (ref "C15") (pin "2") (pinfunction "2_2") (pintype "passive"))
      (node (ref "C16") (pin "2") (pinfunction "2_2") (pintype "passive"))
      (node (ref "C17") (pin "2") (pinfunction "2_2") (pintype "passive"))
      (node (ref "C18") (pin "2") (pinfunction "2_2") (pintype "passive"))
      (node (ref "C19") (pin "2") (pinfunction "2_2") (pintype "passive"))
      (node (ref "C2") (pin "2") (pinfunction "2_2") (pintype "passive"))
      (node (ref "C20") (pin "2") (pinfunction "2_2") (pintype "passive"))
      (node (ref "C21") (pin "-") (pinfunction "-_-") (pintype "passive"))
      (node (ref "C22") (pin "1") (pinfunction "1_1") (pintype "passive"))
      (node (ref "C23") (pin "1") (pinfunction "1_1") (pintype "passive"))
      (node (ref "C24") (pin "1") (pinfunction "1_1") (pintype "passive"))
      (node (ref "C25") (pin "1") (pinfunction "1_1") (pintype "passive"))
      (node (ref "C26") (pin "1") (pinfunction "1_1") (pintype "passive"))
      (node (ref "C27") (pin "1") (pinfunction "1_1") (pintype "passive"))
      (node (ref "C28") (pin "1") (pinfunction "1_1") (pintype "passive"))
      (node (ref "C29") (pin "1") (pinfunction "1_1") (pintype "passive"))
      (node (ref "C3") (pin "2") (pinfunction "2_2") (pintype "passive"))
      (node (ref "C30") (pin "1") (pinfunction "1_1") (pintype "passive"))
      (node (ref "C4") (pin "1") (pinfunction "1_1") (pintype "passive"))
      (node (ref "C5") (pin "1") (pinfunction "1_1") (pintype "passive"))
      (node (ref "C6") (pin "1") (pinfunction "1_1") (pintype "passive"))
      (node (ref "C7") (pin "1") (pinfunction "1_1") (pintype "passive"))
      (node (ref "C8") (pin "1") (pinfunction "1_1") (pintype "passive"))
      (node (ref "C9") (pin "1") (pinfunction "1_1") (pintype "passive"))
      (node (ref "IC1") (pin "21") (pinfunction "GND_21") (pintype "power_in"))
      (node (ref "IC1") (pin "3") (pinfunction "GND_3") (pintype "power_in"))
      (node (ref "IC1") (pin "5") (pinfunction "GND_5") (pintype "power_in"))
      (node (ref "IC10") (pin "18") (pinfunction "GND_18") (pintype "power_in"))
      (node (ref "IC10") (pin "21") (pinfunction "GND_21") (pintype "power_in"))
      (node (ref "IC10") (pin "25") (pinfunction "GND_25") (pintype "power_in"))
      (node (ref "IC10") (pin "26") (pinfunction "TEST_26") (pintype "input"))
      (node (ref "IC10") (pin "7") (pinfunction "GND_7") (pintype "power_in"))
      (node (ref "IC11") (pin "PB") (pinfunction "A1_PB") (pintype "input"))
      (node (ref "IC11") (pin "PC") (pinfunction "A2_PC") (pintype "input"))
      (node (ref "IC11") (pin "PD") (pinfunction "GND_PD") (pintype "power_in"))
      (node (ref "IC12") (pin "2") (pinfunction "VSSA_2") (pintype "power_in"))
      (node (ref "IC13") (pin "GND") (pinfunction "GND_GND") (pintype "input"))
      (node (ref "IC14") (pin "18") (pinfunction "GND1_18") (pintype "power_in"))
      (node (ref "IC14") (pin "28") (pinfunction "GND_28") (pintype "power_in"))
      (node (ref "IC14") (pin "39") (pinfunction "GND2_39") (pintype "power_in"))
      (node (ref "IC14") (pin "6") (pinfunction "GND_6") (pintype "power_in"))
      (node (ref "IC2") (pin "1") (pinfunction "OC_1") (pintype "input"))
      (node (ref "IC3") (pin "1") (pinfunction "OC_1") (pintype "input"))
      (node (ref "IC4") (pin "1") (pinfunction "OC_1") (pintype "input"))
      (node (ref "IC5") (pin "1") (pinfunction "OC_1") (pintype "input"))
      (node (ref "IC6") (pin "1") (pinfunction "OC_1") (pintype "input"))
      (node (ref "IC7") (pin "1") (pinfunction "OC_1") (pintype "input"))
      (node (ref "IC8") (pin "1") (pinfunction "OC_1") (pintype "input"))
      (node (ref "IC9") (pin "1") (pinfunction "OC_1") (pintype "input"))
      (node (ref "JP1") (pin "9") (pinfunction "GND_9") (pintype "power_in"))
      (node (ref "JP3") (pin "10") (pinfunction "GND_10") (pintype "power_in"))
      (node (ref "JP3") (pin "4") (pinfunction "GND_4") (pintype "power_in"))
      (node (ref "JP3") (pin "6") (pinfunction "GND_6") (pintype "power_in"))
      (node (ref "JP3") (pin "8") (pinfunction "GND_8") (pintype "power_in"))
      (node (ref "JP6") (pin "10") (pinfunction "GND_10") (pintype "power_in"))
      (node (ref "JP6") (pin "4") (pinfunction "GND_4") (pintype "power_in"))
      (node (ref "JP6") (pin "6") (pinfunction "GND_6") (pintype "power_in"))
      (node (ref "JP6") (pin "8") (pinfunction "GND_8") (pintype "power_in"))
      (node (ref "R10") (pin "2") (pinfunction "2_2") (pintype "passive"))
      (node (ref "R14") (pin "1") (pinfunction "1_1") (pintype "passive"))
      (node (ref "R18") (pin "E") (pinfunction "E_E") (pintype "passive"))
      (node (ref "R21") (pin "1") (pinfunction "1_1") (pintype "passive"))
      (node (ref "R23") (pin "2") (pinfunction "2_2") (pintype "passive"))
      (node (ref "R24") (pin "2") (pinfunction "2_2") (pintype "passive"))
      (node (ref "R25") (pin "2") (pinfunction "2_2") (pintype "passive"))
      (node (ref "R26") (pin "2") (pinfunction "2_2") (pintype "passive"))
      (node (ref "R27") (pin "2") (pinfunction "2_2") (pintype "passive"))
      (node (ref "R28") (pin "2") (pinfunction "2_2") (pintype "passive"))
      (node (ref "R29") (pin "2") (pinfunction "2_2") (pintype "passive"))
      (node (ref "R30") (pin "2") (pinfunction "2_2") (pintype "passive"))
      (node (ref "R31") (pin "1") (pinfunction "1_1") (pintype "passive"))
      (node (ref "U$1") (pin "GND") (pinfunction "GND_GND") (pintype "bidirectional"))
      (node (ref "U$66") (pin "3") (pinfunction "S_3") (pintype "passive"))
      (node (ref "U$67") (pin "3") (pinfunction "S_3") (pintype "passive"))
      (node (ref "U$68") (pin "3") (pinfunction "S_3") (pintype "passive"))
      (node (ref "U$69") (pin "3") (pinfunction "S_3") (pintype "passive"))
      (node (ref "U$70") (pin "3") (pinfunction "S_3") (pintype "passive"))
      (node (ref "U$71") (pin "3") (pinfunction "S_3") (pintype "passive"))
      (node (ref "U$72") (pin "3") (pinfunction "S_3") (pintype "passive"))
      (node (ref "U$73") (pin "3") (pinfunction "S_3") (pintype "passive"))
      (node (ref "U$74") (pin "B") (pinfunction "B_B") (pintype "bidirectional"))
      (node (ref "U$74") (pin "B2") (pinfunction "B2_B2") (pintype "bidirectional"))
      (node (ref "X1") (pin "1") (pinfunction "1_1") (pintype "passive"))
      (node (ref "X2") (pin "5") (pinfunction "5_5") (pintype "input"))
    )
    (net (code "2") (name "Net-(C13-Pad1)") (class "Default")
      (node (ref "C13") (pin "1") (pinfunction "1_1") (pintype "passive"))
      (node (ref "R16") (pin "2") (pinfunction "2_2") (pintype "passive"))
      (node (ref "R17") (pin "2") (pinfunction "2_2") (pintype "passive"))
    )
    (net (code "3") (name "Net-(C19-Pad1)") (class "Default")
      (node (ref "C19") (pin "1") (pinfunction "1_1") (pintype "passive"))
      (node (ref "IC13") (pin "OUT") (pinfunction "OUT_OUT") (pintype "passive"))
      (node (ref "JP2") (pin "1") (pinfunction "1_1") (pintype "passive"))
    )
    (net (code "4") (name "Net-(C20-Pad1)") (class "Default")
      (node (ref "C20") (pin "1") (pinfunction "1_1") (pintype "passive"))
      (node (ref "C21") (pin "+") (pinfunction "+_+") (pintype "passive"))
      (node (ref "IC13") (pin "IN") (pinfunction "IN_IN") (pintype "input"))
      (node (ref "X1") (pin "2") (pinfunction "2_2") (pintype "passive"))
    )
    (net (code "5") (name "Net-(IC1-AREF)") (class "Default")
      (node (ref "C18") (pin "1") (pinfunction "1_1") (pintype "passive"))
      (node (ref "IC1") (pin "20") (pinfunction "AREF_20") (pintype "passive"))
    )
    (net (code "6") (name "Net-(IC1-PB1(OC1A))") (class "Default")
      (node (ref "IC1") (pin "13") (pinfunction "PB1(OC1A)_13") (pintype "bidirectional"))
      (node (ref "LED1") (pin "A") (pinfunction "A_A") (pintype "passive"))
    )
    (net (code "7") (name "Net-(IC1-PB2(SS{slash}OC1B))") (class "Default")
      (node (ref "IC1") (pin "14") (pinfunction "PB2(SS/OC1B)_14") (pintype "bidirectional"))
      (node (ref "LED65") (pin "A") (pinfunction "A_A") (pintype "passive"))
    )
    (net (code "8") (name "Net-(IC1-PB3(MOSI{slash}OC2))") (class "Default")
      (node (ref "IC1") (pin "15") (pinfunction "PB3(MOSI/OC2)_15") (pintype "bidirectional"))
      (node (ref "JP6") (pin "1") (pinfunction "MOSI_1") (pintype "bidirectional"))
    )
    (net (code "9") (name "Net-(IC1-PB4(MISO))") (class "Default")
      (node (ref "IC1") (pin "16") (pinfunction "PB4(MISO)_16") (pintype "bidirectional"))
      (node (ref "JP6") (pin "9") (pinfunction "MISO_9") (pintype "bidirectional"))
    )
    (net (code "10") (name "Net-(IC1-PB5(SCK))") (class "Default")
      (node (ref "IC1") (pin "17") (pinfunction "PB5(SCK)_17") (pintype "bidirectional"))
      (node (ref "JP6") (pin "7") (pinfunction "SCK_7") (pintype "input"))
    )
    (net (code "11") (name "Net-(IC1-PB6(XTAL1{slash}TOSC1))") (class "Default")
      (node (ref "C15") (pin "1") (pinfunction "1_1") (pintype "passive"))
      (node (ref "IC1") (pin "7") (pinfunction "PB6(XTAL1/TOSC1)_7") (pintype "bidirectional"))
      (node (ref "Q10") (pin "2") (pinfunction "2_2") (pintype "passive"))
    )
    (net (code "12") (name "Net-(IC1-PB7(XTAL2{slash}TOSC2))") (class "Default")
      (node (ref "C14") (pin "1") (pinfunction "1_1") (pintype "passive"))
      (node (ref "IC1") (pin "8") (pinfunction "PB7(XTAL2/TOSC2)_8") (pintype "bidirectional"))
      (node (ref "Q10") (pin "1") (pinfunction "1_1") (pintype "passive"))
    )
    (net (code "13") (name "Net-(IC1-PC0(ADC0))") (class "Default")
      (node (ref "IC1") (pin "23") (pinfunction "PC0(ADC0)_23") (pintype "bidirectional"))
      (node (ref "IC12") (pin "3") (pinfunction "OUT_3") (pintype "output"))
    )
    (net (code "14") (name "Net-(IC1-PC1(ADC1))") (class "Default")
      (node (ref "IC1") (pin "24") (pinfunction "PC1(ADC1)_24") (pintype "bidirectional"))
      (node (ref "R18") (pin "S") (pinfunction "S_S") (pintype "passive"))
    )
    (net (code "15") (name "Net-(IC1-PC2(ADC2))") (class "Default")
      (node (ref "IC1") (pin "25") (pinfunction "PC2(ADC2)_25") (pintype "bidirectional"))
      (node (ref "IC12") (pin "4") (pinfunction "STROBE_4") (pintype "input"))
    )
    (net (code "16") (name "Net-(IC1-PC3(ADC3))") (class "Default")
      (node (ref "IC1") (pin "26") (pinfunction "PC3(ADC3)_26") (pintype "bidirectional"))
      (node (ref "IC12") (pin "7") (pinfunction "RESET_7") (pintype "input"))
    )
    (net (code "17") (name "Net-(IC1-PC4(ADC4{slash}SDA))") (class "Default")
      (node (ref "IC1") (pin "27") (pinfunction "PC4(ADC4/SDA)_27") (pintype "bidirectional"))
      (node (ref "IC11") (pin "PE") (pinfunction "SDA_PE") (pintype "bidirectional"))
      (node (ref "IC14") (pin "20") (pinfunction "PC1(SDA)_20") (pintype "bidirectional"))
      (node (ref "R13") (pin "1") (pinfunction "1_1") (pintype "passive"))
    )
    (net (code "18") (name "Net-(IC1-PC5(ADC5{slash}SCL))") (class "Default")
      (node (ref "IC1") (pin "28") (pinfunction "PC5(ADC5/SCL)_28") (pintype "bidirectional"))
      (node (ref "IC11") (pin "PF") (pinfunction "SCL_PF") (pintype "bidirectional"))
      (node (ref "IC14") (pin "19") (pinfunction "PC0(SCL)_19") (pintype "bidirectional"))
      (node (ref "R12") (pin "1") (pinfunction "1_1") (pintype "passive"))
    )
    (net (code "19") (name "Net-(IC1-PC6({slash}RESET))") (class "Default")
      (node (ref "IC1") (pin "29") (pinfunction "PC6(/RESET)_29") (pintype "bidirectional"))
      (node (ref "JP6") (pin "5") (pinfunction "RESET_5") (pintype "input"))
      (node (ref "R19") (pin "1") (pinfunction "1_1") (pintype "passive"))
    )
    (net (code "20") (name "Net-(IC2A-1Q)") (class "Default")
      (node (ref "IC2") (pin "19") (pinfunction "1Q_19") (pintype "tri_state"))
      (node (ref "R47") (pin "1") (pinfunction "1_1") (pintype "passive"))
    )
    (net (code "21") (name "Net-(IC2A-2Q)") (class "Default")
      (node (ref "IC2") (pin "18") (pinfunction "2Q_18") (pintype "tri_state"))
      (node (ref "R50") (pin "1") (pinfunction "1_1") (pintype "passive"))
    )
    (net (code "22") (name "Net-(IC2A-3Q)") (class "Default")
      (node (ref "IC2") (pin "17") (pinfunction "3Q_17") (pintype "tri_state"))
      (node (ref "R51") (pin "1") (pinfunction "1_1") (pintype "passive"))
    )
    (net (code "23") (name "Net-(IC2A-4Q)") (class "Default")
      (node (ref "IC2") (pin "16") (pinfunction "4Q_16") (pintype "tri_state"))
      (node (ref "R48") (pin "1") (pinfunction "1_1") (pintype "passive"))
    )
    (net (code "24") (name "Net-(IC2A-5Q)") (class "Default")
      (node (ref "IC2") (pin "15") (pinfunction "5Q_15") (pintype "tri_state"))
      (node (ref "R49") (pin "1") (pinfunction "1_1") (pintype "passive"))
    )
    (net (code "25") (name "Net-(IC2A-6Q)") (class "Default")
      (node (ref "IC2") (pin "14") (pinfunction "6Q_14") (pintype "tri_state"))
      (node (ref "R52") (pin "1") (pinfunction "1_1") (pintype "passive"))
    )
    (net (code "26") (name "Net-(IC2A-7Q)") (class "Default")
      (node (ref "IC2") (pin "13") (pinfunction "7Q_13") (pintype "tri_state"))
      (node (ref "R53") (pin "1") (pinfunction "1_1") (pintype "passive"))
    )
    (net (code "27") (name "Net-(IC2A-8Q)") (class "Default")
      (node (ref "IC2") (pin "12") (pinfunction "8Q_12") (pintype "tri_state"))
      (node (ref "R54") (pin "1") (pinfunction "1_1") (pintype "passive"))
    )
    (net (code "28") (name "Net-(IC3A-1Q)") (class "Default")
      (node (ref "IC3") (pin "19") (pinfunction "1Q_19") (pintype "tri_state"))
      (node (ref "R55") (pin "1") (pinfunction "1_1") (pintype "passive"))
    )
    (net (code "29") (name "Net-(IC3A-2Q)") (class "Default")
      (node (ref "IC3") (pin "18") (pinfunction "2Q_18") (pintype "tri_state"))
      (node (ref "R58") (pin "1") (pinfunction "1_1") (pintype "passive"))
    )
    (net (code "30") (name "Net-(IC3A-3Q)") (class "Default")
      (node (ref "IC3") (pin "17") (pinfunction "3Q_17") (pintype "tri_state"))
      (node (ref "R59") (pin "1") (pinfunction "1_1") (pintype "passive"))
    )
    (net (code "31") (name "Net-(IC3A-4Q)") (class "Default")
      (node (ref "IC3") (pin "16") (pinfunction "4Q_16") (pintype "tri_state"))
      (node (ref "R56") (pin "1") (pinfunction "1_1") (pintype "passive"))
    )
    (net (code "32") (name "Net-(IC3A-5Q)") (class "Default")
      (node (ref "IC3") (pin "15") (pinfunction "5Q_15") (pintype "tri_state"))
      (node (ref "R57") (pin "1") (pinfunction "1_1") (pintype "passive"))
    )
    (net (code "33") (name "Net-(IC3A-6Q)") (class "Default")
      (node (ref "IC3") (pin "14") (pinfunction "6Q_14") (pintype "tri_state"))
      (node (ref "R60") (pin "1") (pinfunction "1_1") (pintype "passive"))
    )
    (net (code "34") (name "Net-(IC3A-7Q)") (class "Default")
      (node (ref "IC3") (pin "13") (pinfunction "7Q_13") (pintype "tri_state"))
      (node (ref "R61") (pin "1") (pinfunction "1_1") (pintype "passive"))
    )
    (net (code "35") (name "Net-(IC3A-8Q)") (class "Default")
      (node (ref "IC3") (pin "12") (pinfunction "8Q_12") (pintype "tri_state"))
      (node (ref "R62") (pin "1") (pinfunction "1_1") (pintype "passive"))
    )
    (net (code "36") (name "Net-(IC4A-1Q)") (class "Default")
      (node (ref "IC4") (pin "19") (pinfunction "1Q_19") (pintype "tri_state"))
      (node (ref "R63") (pin "1") (pinfunction "1_1") (pintype "passive"))
    )
    (net (code "37") (name "Net-(IC4A-2Q)") (class "Default")
      (node (ref "IC4") (pin "18") (pinfunction "2Q_18") (pintype "tri_state"))
      (node (ref "R66") (pin "1") (pinfunction "1_1") (pintype "passive"))
    )
    (net (code "38") (name "Net-(IC4A-3Q)") (class "Default")
      (node (ref "IC4") (pin "17") (pinfunction "3Q_17") (pintype "tri_state"))
      (node (ref "R67") (pin "1") (pinfunction "1_1") (pintype "passive"))
    )
    (net (code "39") (name "Net-(IC4A-4Q)") (class "Default")
      (node (ref "IC4") (pin "16") (pinfunction "4Q_16") (pintype "tri_state"))
      (node (ref "R64") (pin "1") (pinfunction "1_1") (pintype "passive"))
    )
    (net (code "40") (name "Net-(IC4A-5Q)") (class "Default")
      (node (ref "IC4") (pin "15") (pinfunction "5Q_15") (pintype "tri_state"))
      (node (ref "R65") (pin "1") (pinfunction "1_1") (pintype "passive"))
    )
    (net (code "41") (name "Net-(IC4A-6Q)") (class "Default")
      (node (ref "IC4") (pin "14") (pinfunction "6Q_14") (pintype "tri_state"))
      (node (ref "R68") (pin "1") (pinfunction "1_1") (pintype "passive"))
    )
    (net (code "42") (name "Net-(IC4A-7Q)") (class "Default")
      (node (ref "IC4") (pin "13") (pinfunction "7Q_13") (pintype "tri_state"))
      (node (ref "R69") (pin "1") (pinfunction "1_1") (pintype "passive"))
    )
    (net (code "43") (name "Net-(IC4A-8Q)") (class "Default")
      (node (ref "IC4") (pin "12") (pinfunction "8Q_12") (pintype "tri_state"))
      (node (ref "R70") (pin "1") (pinfunction "1_1") (pintype "passive"))
    )
    (net (code "44") (name "Net-(IC5A-1Q)") (class "Default")
      (node (ref "IC5") (pin "19") (pinfunction "1Q_19") (pintype "tri_state"))
      (node (ref "R71") (pin "1") (pinfunction "1_1") (pintype "passive"))
    )
    (net (code "45") (name "Net-(IC5A-2Q)") (class "Default")
      (node (ref "IC5") (pin "18") (pinfunction "2Q_18") (pintype "tri_state"))
      (node (ref "R74") (pin "1") (pinfunction "1_1") (pintype "passive"))
    )
    (net (code "46") (name "Net-(IC5A-3Q)") (class "Default")
      (node (ref "IC5") (pin "17") (pinfunction "3Q_17") (pintype "tri_state"))
      (node (ref "R75") (pin "1") (pinfunction "1_1") (pintype "passive"))
    )
    (net (code "47") (name "Net-(IC5A-4Q)") (class "Default")
      (node (ref "IC5") (pin "16") (pinfunction "4Q_16") (pintype "tri_state"))
      (node (ref "R72") (pin "1") (pinfunction "1_1") (pintype "passive"))
    )
    (net (code "48") (name "Net-(IC5A-5Q)") (class "Default")
      (node (ref "IC5") (pin "15") (pinfunction "5Q_15") (pintype "tri_state"))
      (node (ref "R73") (pin "1") (pinfunction "1_1") (pintype "passive"))
    )
    (net (code "49") (name "Net-(IC5A-6Q)") (class "Default")
      (node (ref "IC5") (pin "14") (pinfunction "6Q_14") (pintype "tri_state"))
      (node (ref "R76") (pin "1") (pinfunction "1_1") (pintype "passive"))
    )
    (net (code "50") (name "Net-(IC5A-7Q)") (class "Default")
      (node (ref "IC5") (pin "13") (pinfunction "7Q_13") (pintype "tri_state"))
      (node (ref "R77") (pin "1") (pinfunction "1_1") (pintype "passive"))
    )
    (net (code "51") (name "Net-(IC5A-8Q)") (class "Default")
      (node (ref "IC5") (pin "12") (pinfunction "8Q_12") (pintype "tri_state"))
      (node (ref "R78") (pin "1") (pinfunction "1_1") (pintype "passive"))
    )
    (net (code "52") (name "Net-(IC6A-1Q)") (class "Default")
      (node (ref "IC6") (pin "19") (pinfunction "1Q_19") (pintype "tri_state"))
      (node (ref "R79") (pin "1") (pinfunction "1_1") (pintype "passive"))
    )
    (net (code "53") (name "Net-(IC6A-2Q)") (class "Default")
      (node (ref "IC6") (pin "18") (pinfunction "2Q_18") (pintype "tri_state"))
      (node (ref "R82") (pin "1") (pinfunction "1_1") (pintype "passive"))
    )
    (net (code "54") (name "Net-(IC6A-3Q)") (class "Default")
      (node (ref "IC6") (pin "17") (pinfunction "3Q_17") (pintype "tri_state"))
      (node (ref "R83") (pin "1") (pinfunction "1_1") (pintype "passive"))
    )
    (net (code "55") (name "Net-(IC6A-4Q)") (class "Default")
      (node (ref "IC6") (pin "16") (pinfunction "4Q_16") (pintype "tri_state"))
      (node (ref "R80") (pin "1") (pinfunction "1_1") (pintype "passive"))
    )
    (net (code "56") (name "Net-(IC6A-5Q)") (class "Default")
      (node (ref "IC6") (pin "15") (pinfunction "5Q_15") (pintype "tri_state"))
      (node (ref "R81") (pin "1") (pinfunction "1_1") (pintype "passive"))
    )
    (net (code "57") (name "Net-(IC6A-6Q)") (class "Default")
      (node (ref "IC6") (pin "14") (pinfunction "6Q_14") (pintype "tri_state"))
      (node (ref "R84") (pin "1") (pinfunction "1_1") (pintype "passive"))
    )
    (net (code "58") (name "Net-(IC6A-7Q)") (class "Default")
      (node (ref "IC6") (pin "13") (pinfunction "7Q_13") (pintype "tri_state"))
      (node (ref "R85") (pin "1") (pinfunction "1_1") (pintype "passive"))
    )
    (net (code "59") (name "Net-(IC6A-8Q)") (class "Default")
      (node (ref "IC6") (pin "12") (pinfunction "8Q_12") (pintype "tri_state"))
      (node (ref "R86") (pin "1") (pinfunction "1_1") (pintype "passive"))
    )
    (net (code "60") (name "Net-(IC7A-1Q)") (class "Default")
      (node (ref "IC7") (pin "19") (pinfunction "1Q_19") (pintype "tri_state"))
      (node (ref "R39") (pin "1") (pinfunction "1_1") (pintype "passive"))
    )
    (net (code "61") (name "Net-(IC7A-2Q)") (class "Default")
      (node (ref "IC7") (pin "18") (pinfunction "2Q_18") (pintype "tri_state"))
      (node (ref "R42") (pin "1") (pinfunction "1_1") (pintype "passive"))
    )
    (net (code "62") (name "Net-(IC7A-3Q)") (class "Default")
      (node (ref "IC7") (pin "17") (pinfunction "3Q_17") (pintype "tri_state"))
      (node (ref "R43") (pin "1") (pinfunction "1_1") (pintype "passive"))
    )
    (net (code "63") (name "Net-(IC7A-4Q)") (class "Default")
      (node (ref "IC7") (pin "16") (pinfunction "4Q_16") (pintype "tri_state"))
      (node (ref "R40") (pin "1") (pinfunction "1_1") (pintype "passive"))
    )
    (net (code "64") (name "Net-(IC7A-5Q)") (class "Default")
      (node (ref "IC7") (pin "15") (pinfunction "5Q_15") (pintype "tri_state"))
      (node (ref "R41") (pin "1") (pinfunction "1_1") (pintype "passive"))
    )
    (net (code "65") (name "Net-(IC7A-6Q)") (class "Default")
      (node (ref "IC7") (pin "14") (pinfunction "6Q_14") (pintype "tri_state"))
      (node (ref "R44") (pin "1") (pinfunction "1_1") (pintype "passive"))
    )
    (net (code "66") (name "Net-(IC7A-7Q)") (class "Default")
      (node (ref "IC7") (pin "13") (pinfunction "7Q_13") (pintype "tri_state"))
      (node (ref "R45") (pin "1") (pinfunction "1_1") (pintype "passive"))
    )
    (net (code "67") (name "Net-(IC7A-8Q)") (class "Default")
      (node (ref "IC7") (pin "12") (pinfunction "8Q_12") (pintype "tri_state"))
      (node (ref "R46") (pin "1") (pinfunction "1_1") (pintype "passive"))
    )
    (net (code "68") (name "Net-(IC8A-1Q)") (class "Default")
      (node (ref "IC8") (pin "19") (pinfunction "1Q_19") (pintype "tri_state"))
      (node (ref "R87") (pin "1") (pinfunction "1_1") (pintype "passive"))
    )
    (net (code "69") (name "Net-(IC8A-2Q)") (class "Default")
      (node (ref "IC8") (pin "18") (pinfunction "2Q_18") (pintype "tri_state"))
      (node (ref "R90") (pin "1") (pinfunction "1_1") (pintype "passive"))
    )
    (net (code "70") (name "Net-(IC8A-3Q)") (class "Default")
      (node (ref "IC8") (pin "17") (pinfunction "3Q_17") (pintype "tri_state"))
      (node (ref "R91") (pin "1") (pinfunction "1_1") (pintype "passive"))
    )
    (net (code "71") (name "Net-(IC8A-4Q)") (class "Default")
      (node (ref "IC8") (pin "16") (pinfunction "4Q_16") (pintype "tri_state"))
      (node (ref "R88") (pin "1") (pinfunction "1_1") (pintype "passive"))
    )
    (net (code "72") (name "Net-(IC8A-5Q)") (class "Default")
      (node (ref "IC8") (pin "15") (pinfunction "5Q_15") (pintype "tri_state"))
      (node (ref "R89") (pin "1") (pinfunction "1_1") (pintype "passive"))
    )
    (net (code "73") (name "Net-(IC8A-6Q)") (class "Default")
      (node (ref "IC8") (pin "14") (pinfunction "6Q_14") (pintype "tri_state"))
      (node (ref "R92") (pin "1") (pinfunction "1_1") (pintype "passive"))
    )
    (net (code "74") (name "Net-(IC8A-7Q)") (class "Default")
      (node (ref "IC8") (pin "13") (pinfunction "7Q_13") (pintype "tri_state"))
      (node (ref "R93") (pin "1") (pinfunction "1_1") (pintype "passive"))
    )
    (net (code "75") (name "Net-(IC8A-8Q)") (class "Default")
      (node (ref "IC8") (pin "12") (pinfunction "8Q_12") (pintype "tri_state"))
      (node (ref "R94") (pin "1") (pinfunction "1_1") (pintype "passive"))
    )
    (net (code "76") (name "Net-(IC9A-1Q)") (class "Default")
      (node (ref "IC9") (pin "19") (pinfunction "1Q_19") (pintype "tri_state"))
      (node (ref "R95") (pin "1") (pinfunction "1_1") (pintype "passive"))
    )
    (net (code "77") (name "Net-(IC9A-2Q)") (class "Default")
      (node (ref "IC9") (pin "18") (pinfunction "2Q_18") (pintype "tri_state"))
      (node (ref "R98") (pin "1") (pinfunction "1_1") (pintype "passive"))
    )
    (net (code "78") (name "Net-(IC9A-3Q)") (class "Default")
      (node (ref "IC9") (pin "17") (pinfunction "3Q_17") (pintype "tri_state"))
      (node (ref "R99") (pin "1") (pinfunction "1_1") (pintype "passive"))
    )
    (net (code "79") (name "Net-(IC9A-4Q)") (class "Default")
      (node (ref "IC9") (pin "16") (pinfunction "4Q_16") (pintype "tri_state"))
      (node (ref "R96") (pin "1") (pinfunction "1_1") (pintype "passive"))
    )
    (net (code "80") (name "Net-(IC9A-5Q)") (class "Default")
      (node (ref "IC9") (pin "15") (pinfunction "5Q_15") (pintype "tri_state"))
      (node (ref "R97") (pin "1") (pinfunction "1_1") (pintype "passive"))
    )
    (net (code "81") (name "Net-(IC9A-6Q)") (class "Default")
      (node (ref "IC9") (pin "14") (pinfunction "6Q_14") (pintype "tri_state"))
      (node (ref "R100") (pin "1") (pinfunction "1_1") (pintype "passive"))
    )
    (net (code "82") (name "Net-(IC9A-7Q)") (class "Default")
      (node (ref "IC9") (pin "13") (pinfunction "7Q_13") (pintype "tri_state"))
      (node (ref "R101") (pin "1") (pinfunction "1_1") (pintype "passive"))
    )
    (net (code "83") (name "Net-(IC9A-8Q)") (class "Default")
      (node (ref "IC9") (pin "12") (pinfunction "8Q_12") (pintype "tri_state"))
      (node (ref "R102") (pin "1") (pinfunction "1_1") (pintype "passive"))
    )
    (net (code "84") (name "Net-(IC10-3V3OUT)") (class "Default")
      (node (ref "C6") (pin "2") (pinfunction "2_2") (pintype "passive"))
      (node (ref "IC10") (pin "17") (pinfunction "3V3OUT_17") (pintype "output"))
    )
    (net (code "85") (name "Net-(IC10-RXD)") (class "Default")
      (node (ref "IC10") (pin "5") (pinfunction "RXD_5") (pintype "input"))
      (node (ref "IC14") (pin "10") (pinfunction "(TXD)PD1_10") (pintype "bidirectional"))
    )
    (net (code "86") (name "Net-(IC10-TXD)") (class "Default")
      (node (ref "IC10") (pin "1") (pinfunction "TXD_1") (pintype "output"))
      (node (ref "IC14") (pin "9") (pinfunction "(RXD)PD0_9") (pintype "bidirectional"))
    )
    (net (code "87") (name "Net-(IC10-USBDM)") (class "Default")
      (node (ref "IC10") (pin "16") (pinfunction "USBDM_16") (pintype "bidirectional"))
      (node (ref "X2") (pin "2") (pinfunction "2_2") (pintype "input"))
    )
    (net (code "88") (name "Net-(IC10-USBDP)") (class "Default")
      (node (ref "IC10") (pin "15") (pinfunction "USBDP_15") (pintype "bidirectional"))
      (node (ref "X2") (pin "3") (pinfunction "3_3") (pintype "input"))
    )
    (net (code "89") (name "Net-(IC10-~{RESET})") (class "Default")
      (node (ref "IC10") (pin "19") (pinfunction "~{RESET}_19") (pintype "input"))
      (node (ref "R10") (pin "1") (pinfunction "1_1") (pintype "passive"))
      (node (ref "R11") (pin "1") (pinfunction "1_1") (pintype "passive"))
    )
    (net (code "90") (name "Net-(IC11-WP)") (class "Default")
      (node (ref "IC11") (pin "PG") (pinfunction "WP_PG") (pintype "input"))
      (node (ref "R14") (pin "2") (pinfunction "2_2") (pintype "passive"))
    )
    (net (code "91") (name "Net-(IC12-CKIN)") (class "Default")
      (node (ref "C12") (pin "1") (pinfunction "1_1") (pintype "passive"))
      (node (ref "IC12") (pin "8") (pinfunction "CKIN_8") (pintype "input"))
      (node (ref "R15") (pin "2") (pinfunction "2_2") (pintype "passive"))
    )
    (net (code "92") (name "Net-(IC12-GND)") (class "Default")
      (node (ref "C11") (pin "1") (pinfunction "1_1") (pintype "passive"))
      (node (ref "IC12") (pin "6") (pinfunction "GND_6") (pintype "power_in"))
    )
    (net (code "93") (name "Net-(IC12-IN)") (class "Default")
      (node (ref "C13") (pin "2") (pinfunction "2_2") (pintype "passive"))
      (node (ref "IC12") (pin "5") (pinfunction "IN_5") (pintype "input"))
    )
    (net (code "94") (name "Net-(IC14-(ADC0)PA0)") (class "Default")
      (node (ref "IC14") (pin "37") (pinfunction "(ADC0)PA0_37") (pintype "bidirectional"))
      (node (ref "IC2") (pin "2") (pinfunction "1D_2") (pintype "input"))
      (node (ref "IC3") (pin "2") (pinfunction "1D_2") (pintype "input"))
      (node (ref "IC4") (pin "2") (pinfunction "1D_2") (pintype "input"))
      (node (ref "IC5") (pin "2") (pinfunction "1D_2") (pintype "input"))
      (node (ref "IC6") (pin "2") (pinfunction "1D_2") (pintype "input"))
      (node (ref "IC7") (pin "2") (pinfunction "1D_2") (pintype "input"))
      (node (ref "IC8") (pin "2") (pinfunction "1D_2") (pintype "input"))
      (node (ref "IC9") (pin "2") (pinfunction "1D_2") (pintype "input"))
    )
    (net (code "95") (name "Net-(IC14-(ADC1)PA1)") (class "Default")
      (node (ref "IC14") (pin "36") (pinfunction "(ADC1)PA1_36") (pintype "bidirectional"))
      (node (ref "IC2") (pin "3") (pinfunction "2D_3") (pintype "input"))
      (node (ref "IC3") (pin "3") (pinfunction "2D_3") (pintype "input"))
      (node (ref "IC4") (pin "3") (pinfunction "2D_3") (pintype "input"))
      (node (ref "IC5") (pin "3") (pinfunction "2D_3") (pintype "input"))
      (node (ref "IC6") (pin "3") (pinfunction "2D_3") (pintype "input"))
      (node (ref "IC7") (pin "3") (pinfunction "2D_3") (pintype "input"))
      (node (ref "IC8") (pin "3") (pinfunction "2D_3") (pintype "input"))
      (node (ref "IC9") (pin "3") (pinfunction "2D_3") (pintype "input"))
    )
    (net (code "96") (name "Net-(IC14-(ADC2)PA2)") (class "Default")
      (node (ref "IC14") (pin "35") (pinfunction "(ADC2)PA2_35") (pintype "bidirectional"))
      (node (ref "IC2") (pin "4") (pinfunction "3D_4") (pintype "input"))
      (node (ref "IC3") (pin "4") (pinfunction "3D_4") (pintype "input"))
      (node (ref "IC4") (pin "4") (pinfunction "3D_4") (pintype "input"))
      (node (ref "IC5") (pin "4") (pinfunction "3D_4") (pintype "input"))
      (node (ref "IC6") (pin "4") (pinfunction "3D_4") (pintype "input"))
      (node (ref "IC7") (pin "4") (pinfunction "3D_4") (pintype "input"))
      (node (ref "IC8") (pin "4") (pinfunction "3D_4") (pintype "input"))
      (node (ref "IC9") (pin "4") (pinfunction "3D_4") (pintype "input"))
    )
    (net (code "97") (name "Net-(IC14-(ADC3)PA3)") (class "Default")
      (node (ref "IC14") (pin "34") (pinfunction "(ADC3)PA3_34") (pintype "bidirectional"))
      (node (ref "IC2") (pin "5") (pinfunction "4D_5") (pintype "input"))
      (node (ref "IC3") (pin "5") (pinfunction "4D_5") (pintype "input"))
      (node (ref "IC4") (pin "5") (pinfunction "4D_5") (pintype "input"))
      (node (ref "IC5") (pin "5") (pinfunction "4D_5") (pintype "input"))
      (node (ref "IC6") (pin "5") (pinfunction "4D_5") (pintype "input"))
      (node (ref "IC7") (pin "5") (pinfunction "4D_5") (pintype "input"))
      (node (ref "IC8") (pin "5") (pinfunction "4D_5") (pintype "input"))
      (node (ref "IC9") (pin "5") (pinfunction "4D_5") (pintype "input"))
    )
    (net (code "98") (name "Net-(IC14-(ADC4)PA4)") (class "Default")
      (node (ref "IC14") (pin "33") (pinfunction "(ADC4)PA4_33") (pintype "bidirectional"))
      (node (ref "IC2") (pin "6") (pinfunction "5D_6") (pintype "input"))
      (node (ref "IC3") (pin "6") (pinfunction "5D_6") (pintype "input"))
      (node (ref "IC4") (pin "6") (pinfunction "5D_6") (pintype "input"))
      (node (ref "IC5") (pin "6") (pinfunction "5D_6") (pintype "input"))
      (node (ref "IC6") (pin "6") (pinfunction "5D_6") (pintype "input"))
      (node (ref "IC7") (pin "6") (pinfunction "5D_6") (pintype "input"))
      (node (ref "IC8") (pin "6") (pinfunction "5D_6") (pintype "input"))
      (node (ref "IC9") (pin "6") (pinfunction "5D_6") (pintype "input"))
    )
    (net (code "99") (name "Net-(IC14-(ADC5)PA5)") (class "Default")
      (node (ref "IC14") (pin "32") (pinfunction "(ADC5)PA5_32") (pintype "bidirectional"))
      (node (ref "IC2") (pin "7") (pinfunction "6D_7") (pintype "input"))
      (node (ref "IC3") (pin "7") (pinfunction "6D_7") (pintype "input"))
      (node (ref "IC4") (pin "7") (pinfunction "6D_7") (pintype "input"))
      (node (ref "IC5") (pin "7") (pinfunction "6D_7") (pintype "input"))
      (node (ref "IC6") (pin "7") (pinfunction "6D_7") (pintype "input"))
      (node (ref "IC7") (pin "7") (pinfunction "6D_7") (pintype "input"))
      (node (ref "IC8") (pin "7") (pinfunction "6D_7") (pintype "input"))
      (node (ref "IC9") (pin "7") (pinfunction "6D_7") (pintype "input"))
    )
    (net (code "100") (name "Net-(IC14-(ADC6)PA6)") (class "Default")
      (node (ref "IC14") (pin "31") (pinfunction "(ADC6)PA6_31") (pintype "bidirectional"))
      (node (ref "IC2") (pin "8") (pinfunction "7D_8") (pintype "input"))
      (node (ref "IC3") (pin "8") (pinfunction "7D_8") (pintype "input"))
      (node (ref "IC4") (pin "8") (pinfunction "7D_8") (pintype "input"))
      (node (ref "IC5") (pin "8") (pinfunction "7D_8") (pintype "input"))
      (node (ref "IC6") (pin "8") (pinfunction "7D_8") (pintype "input"))
      (node (ref "IC7") (pin "8") (pinfunction "7D_8") (pintype "input"))
      (node (ref "IC8") (pin "8") (pinfunction "7D_8") (pintype "input"))
      (node (ref "IC9") (pin "8") (pinfunction "7D_8") (pintype "input"))
    )
    (net (code "101") (name "Net-(IC14-(ADC7)PA7)") (class "Default")
      (node (ref "IC14") (pin "30") (pinfunction "(ADC7)PA7_30") (pintype "bidirectional"))
      (node (ref "IC2") (pin "9") (pinfunction "8D_9") (pintype "input"))
      (node (ref "IC3") (pin "9") (pinfunction "8D_9") (pintype "input"))
      (node (ref "IC4") (pin "9") (pinfunction "8D_9") (pintype "input"))
      (node (ref "IC5") (pin "9") (pinfunction "8D_9") (pintype "input"))
      (node (ref "IC6") (pin "9") (pinfunction "8D_9") (pintype "input"))
      (node (ref "IC7") (pin "9") (pinfunction "8D_9") (pintype "input"))
      (node (ref "IC8") (pin "9") (pinfunction "8D_9") (pintype "input"))
      (node (ref "IC9") (pin "9") (pinfunction "8D_9") (pintype "input"))
    )
    (net (code "102") (name "Net-(IC14-(AIN0{slash}INT2)PB2)") (class "Default")
      (node (ref "IC14") (pin "42") (pinfunction "(AIN0/INT2)PB2_42") (pintype "bidirectional"))
      (node (ref "IC8") (pin "11") (pinfunction "C_11") (pintype "input"))
    )
    (net (code "103") (name "Net-(IC14-(AIN1{slash}OC0)PB3)") (class "Default")
      (node (ref "IC14") (pin "43") (pinfunction "(AIN1/OC0)PB3_43") (pintype "bidirectional"))
      (node (ref "R9") (pin "1") (pinfunction "1_1") (pintype "passive"))
    )
    (net (code "104") (name "Net-(IC14-(ICP)PD6)") (class "Default")
      (node (ref "IC14") (pin "15") (pinfunction "(ICP)PD6_15") (pintype "bidirectional"))
      (node (ref "R3") (pin "1") (pinfunction "1_1") (pintype "passive"))
    )
    (net (code "105") (name "Net-(IC14-(INT0)PD2)") (class "Default")
      (node (ref "IC14") (pin "11") (pinfunction "(INT0)PD2_11") (pintype "bidirectional"))
      (node (ref "R7") (pin "1") (pinfunction "1_1") (pintype "passive"))
    )
    (net (code "106") (name "Net-(IC14-(INT1)PD3)") (class "Default")
      (node (ref "IC14") (pin "12") (pinfunction "(INT1)PD3_12") (pintype "bidirectional"))
      (node (ref "R6") (pin "1") (pinfunction "1_1") (pintype "passive"))
    )
    (net (code "107") (name "Net-(IC14-(MISO)PB6)") (class "Default")
      (node (ref "IC14") (pin "2") (pinfunction "(MISO)PB6_2") (pintype "bidirectional"))
      (node (ref "JP3") (pin "9") (pinfunction "MISO_9") (pintype "bidirectional"))
    )
    (net (code "108") (name "Net-(IC14-(MOSI)PB5)") (class "Default")
      (node (ref "IC14") (pin "1") (pinfunction "(MOSI)PB5_1") (pintype "bidirectional"))
      (node (ref "JP3") (pin "1") (pinfunction "MOSI_1") (pintype "bidirectional"))
    )
    (net (code "109") (name "Net-(IC14-(OC1A)PD5)") (class "Default")
      (node (ref "IC14") (pin "14") (pinfunction "(OC1A)PD5_14") (pintype "bidirectional"))
      (node (ref "R4") (pin "1") (pinfunction "1_1") (pintype "passive"))
    )
    (net (code "110") (name "Net-(IC14-(OC1B)PD4)") (class "Default")
      (node (ref "IC14") (pin "13") (pinfunction "(OC1B)PD4_13") (pintype "bidirectional"))
      (node (ref "R5") (pin "1") (pinfunction "1_1") (pintype "passive"))
    )
    (net (code "111") (name "Net-(IC14-(OC2)PD7)") (class "Default")
      (node (ref "IC14") (pin "16") (pinfunction "(OC2)PD7_16") (pintype "bidirectional"))
      (node (ref "R2") (pin "1") (pinfunction "1_1") (pintype "passive"))
    )
    (net (code "112") (name "Net-(IC14-(SCK)PB7)") (class "Default")
      (node (ref "IC14") (pin "3") (pinfunction "(SCK)PB7_3") (pintype "bidirectional"))
      (node (ref "JP3") (pin "7") (pinfunction "SCK_7") (pintype "input"))
    )
    (net (code "113") (name "Net-(IC14-(SS)PB4)") (class "Default")
      (node (ref "IC14") (pin "44") (pinfunction "(SS)PB4_44") (pintype "bidirectional"))
      (node (ref "R8") (pin "1") (pinfunction "1_1") (pintype "passive"))
    )
    (net (code "114") (name "Net-(IC14-(T0{slash}XCK)PB0)") (class "Default")
      (node (ref "IC14") (pin "40") (pinfunction "(T0/XCK)PB0_40") (pintype "bidirectional"))
      (node (ref "R20") (pin "2") (pinfunction "2_2") (pintype "passive"))
      (node (ref "U$74") (pin "A") (pinfunction "A_A") (pintype "bidirectional"))
      (node (ref "U$74") (pin "A2") (pinfunction "A2_A2") (pintype "bidirectional"))
    )
    (net (code "115") (name "Net-(IC14-(T1)PB1)") (class "Default")
      (node (ref "IC14") (pin "41") (pinfunction "(T1)PB1_41") (pintype "bidirectional"))
      (node (ref "IC9") (pin "11") (pinfunction "C_11") (pintype "input"))
    )
    (net (code "116") (name "Net-(IC14-(TCK)PC2)") (class "Default")
      (node (ref "IC14") (pin "21") (pinfunction "(TCK)PC2_21") (pintype "bidirectional"))
      (node (ref "IC6") (pin "11") (pinfunction "C_11") (pintype "input"))
    )
    (net (code "117") (name "Net-(IC14-(TDI)PC5)") (class "Default")
      (node (ref "IC14") (pin "24") (pinfunction "(TDI)PC5_24") (pintype "bidirectional"))
      (node (ref "IC3") (pin "11") (pinfunction "C_11") (pintype "input"))
    )
    (net (code "118") (name "Net-(IC14-(TDO)PC4)") (class "Default")
      (node (ref "IC14") (pin "23") (pinfunction "(TDO)PC4_23") (pintype "bidirectional"))
      (node (ref "IC4") (pin "11") (pinfunction "C_11") (pintype "input"))
    )
    (net (code "119") (name "Net-(IC14-(TMS)PC3)") (class "Default")
      (node (ref "IC14") (pin "22") (pinfunction "(TMS)PC3_22") (pintype "bidirectional"))
      (node (ref "IC5") (pin "11") (pinfunction "C_11") (pintype "input"))
    )
    (net (code "120") (name "Net-(IC14-(TOSC1)PC6)") (class "Default")
      (node (ref "IC14") (pin "25") (pinfunction "(TOSC1)PC6_25") (pintype "bidirectional"))
      (node (ref "IC2") (pin "11") (pinfunction "C_11") (pintype "input"))
    )
    (net (code "121") (name "Net-(IC14-(TOSC2)PC7)") (class "Default")
      (node (ref "IC14") (pin "26") (pinfunction "(TOSC2)PC7_26") (pintype "bidirectional"))
      (node (ref "IC7") (pin "11") (pinfunction "C_11") (pintype "input"))
    )
    (net (code "122") (name "Net-(IC14-AREF)") (class "Default")
      (node (ref "C2") (pin "1") (pinfunction "1_1") (pintype "passive"))
      (node (ref "IC14") (pin "29") (pinfunction "AREF_29") (pintype "passive"))
    )
    (net (code "123") (name "Net-(IC14-RESET)") (class "Default")
      (node (ref "IC14") (pin "4") (pinfunction "RESET_4") (pintype "input"))
      (node (ref "JP3") (pin "5") (pinfunction "RESET_5") (pintype "input"))
      (node (ref "R1") (pin "2") (pinfunction "2_2") (pintype "passive"))
    )
    (net (code "124") (name "Net-(IC14-XTAL1)") (class "Default")
      (node (ref "C4") (pin "2") (pinfunction "2_2") (pintype "passive"))
      (node (ref "IC14") (pin "8") (pinfunction "XTAL1_8") (pintype "bidirectional"))
      (node (ref "Q1") (pin "1") (pinfunction "1_1") (pintype "passive"))
    )
    (net (code "125") (name "Net-(IC14-XTAL2)") (class "Default")
      (node (ref "C5") (pin "2") (pinfunction "2_2") (pintype "passive"))
      (node (ref "IC14") (pin "7") (pinfunction "XTAL2_7") (pintype "bidirectional"))
      (node (ref "Q1") (pin "2") (pinfunction "2_2") (pintype "passive"))
    )
    (net (code "126") (name "Net-(JP1-P0)") (class "Default")
      (node (ref "JP1") (pin "1") (pinfunction "P0_1") (pintype "bidirectional"))
      (node (ref "U$66") (pin "2") (pinfunction "D_2") (pintype "passive"))
    )
    (net (code "127") (name "Net-(JP1-P1)") (class "Default")
      (node (ref "JP1") (pin "2") (pinfunction "P1_2") (pintype "bidirectional"))
      (node (ref "U$67") (pin "2") (pinfunction "D_2") (pintype "passive"))
    )
    (net (code "128") (name "Net-(JP1-P2)") (class "Default")
      (node (ref "JP1") (pin "3") (pinfunction "P2_3") (pintype "bidirectional"))
      (node (ref "U$68") (pin "2") (pinfunction "D_2") (pintype "passive"))
    )
    (net (code "129") (name "Net-(JP1-P3)") (class "Default")
      (node (ref "JP1") (pin "4") (pinfunction "P3_4") (pintype "bidirectional"))
      (node (ref "U$69") (pin "2") (pinfunction "D_2") (pintype "passive"))
    )
    (net (code "130") (name "Net-(JP1-P4)") (class "Default")
      (node (ref "JP1") (pin "5") (pinfunction "P4_5") (pintype "bidirectional"))
      (node (ref "U$70") (pin "2") (pinfunction "D_2") (pintype "passive"))
    )
    (net (code "131") (name "Net-(JP1-P5)") (class "Default")
      (node (ref "JP1") (pin "6") (pinfunction "P5_6") (pintype "bidirectional"))
      (node (ref "U$71") (pin "2") (pinfunction "D_2") (pintype "passive"))
    )
    (net (code "132") (name "Net-(JP1-P6)") (class "Default")
      (node (ref "JP1") (pin "7") (pinfunction "P6_7") (pintype "bidirectional"))
      (node (ref "U$72") (pin "2") (pinfunction "D_2") (pintype "passive"))
    )
    (net (code "133") (name "Net-(JP1-P7)") (class "Default")
      (node (ref "JP1") (pin "8") (pinfunction "P7_8") (pintype "bidirectional"))
      (node (ref "U$73") (pin "2") (pinfunction "D_2") (pintype "passive"))
    )
    (net (code "134") (name "Net-(LED1-PadC)") (class "Default")
      (node (ref "LED1") (pin "C") (pinfunction "C_C") (pintype "passive"))
      (node (ref "R31") (pin "2") (pinfunction "2_2") (pintype "passive"))
    )
    (net (code "135") (name "Net-(LED65-PadC)") (class "Default")
      (node (ref "LED65") (pin "C") (pinfunction "C_C") (pintype "passive"))
      (node (ref "R21") (pin "2") (pinfunction "2_2") (pintype "passive"))
    )
    (net (code "136") (name "Net-(R11-Pad2)") (class "Default")
      (node (ref "R11") (pin "2") (pinfunction "2_2") (pintype "passive"))
      (node (ref "X2") (pin "1") (pinfunction "1_1") (pintype "input"))
    )
    (net (code "137") (name "Net-(U$1-L)") (class "Default")
      (node (ref "R17") (pin "1") (pinfunction "1_1") (pintype "passive"))
      (node (ref "U$1") (pin "LEFT") (pinfunction "L_LEFT") (pintype "bidirectional"))
    )
    (net (code "138") (name "Net-(U$1-R)") (class "Default")
      (node (ref "R16") (pin "1") (pinfunction "1_1") (pintype "passive"))
      (node (ref "U$1") (pin "RIGHT") (pinfunction "R_RIGHT") (pintype "bidirectional"))
    )
    (net (code "139") (name "Net-(U$2-B)") (class "Default")
      (node (ref "R39") (pin "2") (pinfunction "2_2") (pintype "passive"))
      (node (ref "U$2") (pin "P$1") (pinfunction "B_P$1") (pintype "passive"))
    )
    (net (code "140") (name "Net-(U$2-C)") (class "Default")
      (node (ref "SV1") (pin "1") (pinfunction "1_1") (pintype "passive"))
      (node (ref "U$2") (pin "P$3") (pinfunction "C_P$3") (pintype "passive"))
    )
    (net (code "141") (name "Net-(U$3-B)") (class "Default")
      (node (ref "R40") (pin "2") (pinfunction "2_2") (pintype "passive"))
      (node (ref "U$3") (pin "P$1") (pinfunction "B_P$1") (pintype "passive"))
    )
    (net (code "142") (name "Net-(U$3-C)") (class "Default")
      (node (ref "SV1") (pin "4") (pinfunction "4_4") (pintype "passive"))
      (node (ref "U$3") (pin "P$3") (pinfunction "C_P$3") (pintype "passive"))
    )
    (net (code "143") (name "Net-(U$4-B)") (class "Default")
      (node (ref "R41") (pin "2") (pinfunction "2_2") (pintype "passive"))
      (node (ref "U$4") (pin "P$1") (pinfunction "B_P$1") (pintype "passive"))
    )
    (net (code "144") (name "Net-(U$4-C)") (class "Default")
      (node (ref "SV1") (pin "5") (pinfunction "5_5") (pintype "passive"))
      (node (ref "U$4") (pin "P$3") (pinfunction "C_P$3") (pintype "passive"))
    )
    (net (code "145") (name "Net-(U$5-B)") (class "Default")
      (node (ref "R42") (pin "2") (pinfunction "2_2") (pintype "passive"))
      (node (ref "U$5") (pin "P$1") (pinfunction "B_P$1") (pintype "passive"))
    )
    (net (code "146") (name "Net-(U$5-C)") (class "Default")
      (node (ref "SV1") (pin "2") (pinfunction "2_2") (pintype "passive"))
      (node (ref "U$5") (pin "P$3") (pinfunction "C_P$3") (pintype "passive"))
    )
    (net (code "147") (name "Net-(U$6-B)") (class "Default")
      (node (ref "R43") (pin "2") (pinfunction "2_2") (pintype "passive"))
      (node (ref "U$6") (pin "P$1") (pinfunction "B_P$1") (pintype "passive"))
    )
    (net (code "148") (name "Net-(U$6-C)") (class "Default")
      (node (ref "SV1") (pin "3") (pinfunction "3_3") (pintype "passive"))
      (node (ref "U$6") (pin "P$3") (pinfunction "C_P$3") (pintype "passive"))
    )
    (net (code "149") (name "Net-(U$7-B)") (class "Default")
      (node (ref "R44") (pin "2") (pinfunction "2_2") (pintype "passive"))
      (node (ref "U$7") (pin "P$1") (pinfunction "B_P$1") (pintype "passive"))
    )
    (net (code "150") (name "Net-(U$7-C)") (class "Default")
      (node (ref "SV1") (pin "6") (pinfunction "6_6") (pintype "passive"))
      (node (ref "U$7") (pin "P$3") (pinfunction "C_P$3") (pintype "passive"))
    )
    (net (code "151") (name "Net-(U$8-B)") (class "Default")
      (node (ref "R45") (pin "2") (pinfunction "2_2") (pintype "passive"))
      (node (ref "U$8") (pin "P$1") (pinfunction "B_P$1") (pintype "passive"))
    )
    (net (code "152") (name "Net-(U$8-C)") (class "Default")
      (node (ref "SV1") (pin "7") (pinfunction "7_7") (pintype "passive"))
      (node (ref "U$8") (pin "P$3") (pinfunction "C_P$3") (pintype "passive"))
    )
    (net (code "153") (name "Net-(U$9-B)") (class "Default")
      (node (ref "R46") (pin "2") (pinfunction "2_2") (pintype "passive"))
      (node (ref "U$9") (pin "P$1") (pinfunction "B_P$1") (pintype "passive"))
    )
    (net (code "154") (name "Net-(U$9-C)") (class "Default")
      (node (ref "SV1") (pin "8") (pinfunction "8_8") (pintype "passive"))
      (node (ref "U$9") (pin "P$3") (pinfunction "C_P$3") (pintype "passive"))
    )
    (net (code "155") (name "Net-(U$10-B)") (class "Default")
      (node (ref "R47") (pin "2") (pinfunction "2_2") (pintype "passive"))
      (node (ref "U$10") (pin "P$1") (pinfunction "B_P$1") (pintype "passive"))
    )
    (net (code "156") (name "Net-(U$10-C)") (class "Default")
      (node (ref "SV1") (pin "9") (pinfunction "9_9") (pintype "passive"))
      (node (ref "U$10") (pin "P$3") (pinfunction "C_P$3") (pintype "passive"))
    )
    (net (code "157") (name "Net-(U$11-B)") (class "Default")
      (node (ref "R48") (pin "2") (pinfunction "2_2") (pintype "passive"))
      (node (ref "U$11") (pin "P$1") (pinfunction "B_P$1") (pintype "passive"))
    )
    (net (code "158") (name "Net-(U$11-C)") (class "Default")
      (node (ref "SV1") (pin "12") (pinfunction "12_12") (pintype "passive"))
      (node (ref "U$11") (pin "P$3") (pinfunction "C_P$3") (pintype "passive"))
    )
    (net (code "159") (name "Net-(U$12-B)") (class "Default")
      (node (ref "R49") (pin "2") (pinfunction "2_2") (pintype "passive"))
      (node (ref "U$12") (pin "P$1") (pinfunction "B_P$1") (pintype "passive"))
    )
    (net (code "160") (name "Net-(U$12-C)") (class "Default")
      (node (ref "SV1") (pin "13") (pinfunction "13_13") (pintype "passive"))
      (node (ref "U$12") (pin "P$3") (pinfunction "C_P$3") (pintype "passive"))
    )
    (net (code "161") (name "Net-(U$13-B)") (class "Default")
      (node (ref "R50") (pin "2") (pinfunction "2_2") (pintype "passive"))
      (node (ref "U$13") (pin "P$1") (pinfunction "B_P$1") (pintype "passive"))
    )
    (net (code "162") (name "Net-(U$13-C)") (class "Default")
      (node (ref "SV1") (pin "10") (pinfunction "10_10") (pintype "passive"))
      (node (ref "U$13") (pin "P$3") (pinfunction "C_P$3") (pintype "passive"))
    )
    (net (code "163") (name "Net-(U$14-B)") (class "Default")
      (node (ref "R51") (pin "2") (pinfunction "2_2") (pintype "passive"))
      (node (ref "U$14") (pin "P$1") (pinfunction "B_P$1") (pintype "passive"))
    )
    (net (code "164") (name "Net-(U$14-C)") (class "Default")
      (node (ref "SV1") (pin "11") (pinfunction "11_11") (pintype "passive"))
      (node (ref "U$14") (pin "P$3") (pinfunction "C_P$3") (pintype "passive"))
    )
    (net (code "165") (name "Net-(U$15-B)") (class "Default")
      (node (ref "R52") (pin "2") (pinfunction "2_2") (pintype "passive"))
      (node (ref "U$15") (pin "P$1") (pinfunction "B_P$1") (pintype "passive"))
    )
    (net (code "166") (name "Net-(U$15-C)") (class "Default")
      (node (ref "SV1") (pin "14") (pinfunction "14_14") (pintype "passive"))
      (node (ref "U$15") (pin "P$3") (pinfunction "C_P$3") (pintype "passive"))
    )
    (net (code "167") (name "Net-(U$16-B)") (class "Default")
      (node (ref "R53") (pin "2") (pinfunction "2_2") (pintype "passive"))
      (node (ref "U$16") (pin "P$1") (pinfunction "B_P$1") (pintype "passive"))
    )
    (net (code "168") (name "Net-(U$16-C)") (class "Default")
      (node (ref "SV1") (pin "15") (pinfunction "15_15") (pintype "passive"))
      (node (ref "U$16") (pin "P$3") (pinfunction "C_P$3") (pintype "passive"))
    )
    (net (code "169") (name "Net-(U$17-B)") (class "Default")
      (node (ref "R54") (pin "2") (pinfunction "2_2") (pintype "passive"))
      (node (ref "U$17") (pin "P$1") (pinfunction "B_P$1") (pintype "passive"))
    )
    (net (code "170") (name "Net-(U$17-C)") (class "Default")
      (node (ref "SV1") (pin "16") (pinfunction "16_16") (pintype "passive"))
      (node (ref "U$17") (pin "P$3") (pinfunction "C_P$3") (pintype "passive"))
    )
    (net (code "171") (name "Net-(U$18-B)") (class "Default")
      (node (ref "R55") (pin "2") (pinfunction "2_2") (pintype "passive"))
      (node (ref "U$18") (pin "P$1") (pinfunction "B_P$1") (pintype "passive"))
    )
    (net (code "172") (name "Net-(U$18-C)") (class "Default")
      (node (ref "SV1") (pin "17") (pinfunction "17_17") (pintype "passive"))
      (node (ref "U$18") (pin "P$3") (pinfunction "C_P$3") (pintype "passive"))
    )
    (net (code "173") (name "Net-(U$19-B)") (class "Default")
      (node (ref "R56") (pin "2") (pinfunction "2_2") (pintype "passive"))
      (node (ref "U$19") (pin "P$1") (pinfunction "B_P$1") (pintype "passive"))
    )
    (net (code "174") (name "Net-(U$19-C)") (class "Default")
      (node (ref "SV1") (pin "20") (pinfunction "20_20") (pintype "passive"))
      (node (ref "U$19") (pin "P$3") (pinfunction "C_P$3") (pintype "passive"))
    )
    (net (code "175") (name "Net-(U$20-B)") (class "Default")
      (node (ref "R57") (pin "2") (pinfunction "2_2") (pintype "passive"))
      (node (ref "U$20") (pin "P$1") (pinfunction "B_P$1") (pintype "passive"))
    )
    (net (code "176") (name "Net-(U$20-C)") (class "Default")
      (node (ref "SV1") (pin "21") (pinfunction "21_21") (pintype "passive"))
      (node (ref "U$20") (pin "P$3") (pinfunction "C_P$3") (pintype "passive"))
    )
    (net (code "177") (name "Net-(U$21-B)") (class "Default")
      (node (ref "R58") (pin "2") (pinfunction "2_2") (pintype "passive"))
      (node (ref "U$21") (pin "P$1") (pinfunction "B_P$1") (pintype "passive"))
    )
    (net (code "178") (name "Net-(U$21-C)") (class "Default")
      (node (ref "SV1") (pin "18") (pinfunction "18_18") (pintype "passive"))
      (node (ref "U$21") (pin "P$3") (pinfunction "C_P$3") (pintype "passive"))
    )
    (net (code "179") (name "Net-(U$22-B)") (class "Default")
      (node (ref "R59") (pin "2") (pinfunction "2_2") (pintype "passive"))
      (node (ref "U$22") (pin "P$1") (pinfunction "B_P$1") (pintype "passive"))
    )
    (net (code "180") (name "Net-(U$22-C)") (class "Default")
      (node (ref "SV1") (pin "19") (pinfunction "19_19") (pintype "passive"))
      (node (ref "U$22") (pin "P$3") (pinfunction "C_P$3") (pintype "passive"))
    )
    (net (code "181") (name "Net-(U$23-B)") (class "Default")
      (node (ref "R60") (pin "2") (pinfunction "2_2") (pintype "passive"))
      (node (ref "U$23") (pin "P$1") (pinfunction "B_P$1") (pintype "passive"))
    )
    (net (code "182") (name "Net-(U$23-C)") (class "Default")
      (node (ref "SV1") (pin "22") (pinfunction "22_22") (pintype "passive"))
      (node (ref "U$23") (pin "P$3") (pinfunction "C_P$3") (pintype "passive"))
    )
    (net (code "183") (name "Net-(U$24-B)") (class "Default")
      (node (ref "R61") (pin "2") (pinfunction "2_2") (pintype "passive"))
      (node (ref "U$24") (pin "P$1") (pinfunction "B_P$1") (pintype "passive"))
    )
    (net (code "184") (name "Net-(U$24-C)") (class "Default")
      (node (ref "SV1") (pin "23") (pinfunction "23_23") (pintype "passive"))
      (node (ref "U$24") (pin "P$3") (pinfunction "C_P$3") (pintype "passive"))
    )
    (net (code "185") (name "Net-(U$25-B)") (class "Default")
      (node (ref "R62") (pin "2") (pinfunction "2_2") (pintype "passive"))
      (node (ref "U$25") (pin "P$1") (pinfunction "B_P$1") (pintype "passive"))
    )
    (net (code "186") (name "Net-(U$25-C)") (class "Default")
      (node (ref "SV1") (pin "24") (pinfunction "24_24") (pintype "passive"))
      (node (ref "U$25") (pin "P$3") (pinfunction "C_P$3") (pintype "passive"))
    )
    (net (code "187") (name "Net-(U$26-B)") (class "Default")
      (node (ref "R63") (pin "2") (pinfunction "2_2") (pintype "passive"))
      (node (ref "U$26") (pin "P$1") (pinfunction "B_P$1") (pintype "passive"))
    )
    (net (code "188") (name "Net-(U$26-C)") (class "Default")
      (node (ref "SV1") (pin "25") (pinfunction "25_25") (pintype "passive"))
      (node (ref "U$26") (pin "P$3") (pinfunction "C_P$3") (pintype "passive"))
    )
    (net (code "189") (name "Net-(U$27-B)") (class "Default")
      (node (ref "R64") (pin "2") (pinfunction "2_2") (pintype "passive"))
      (node (ref "U$27") (pin "P$1") (pinfunction "B_P$1") (pintype "passive"))
    )
    (net (code "190") (name "Net-(U$27-C)") (class "Default")
      (node (ref "SV1") (pin "28") (pinfunction "28_28") (pintype "passive"))
      (node (ref "U$27") (pin "P$3") (pinfunction "C_P$3") (pintype "passive"))
    )
    (net (code "191") (name "Net-(U$28-B)") (class "Default")
      (node (ref "R65") (pin "2") (pinfunction "2_2") (pintype "passive"))
      (node (ref "U$28") (pin "P$1") (pinfunction "B_P$1") (pintype "passive"))
    )
    (net (code "192") (name "Net-(U$28-C)") (class "Default")
      (node (ref "SV1") (pin "29") (pinfunction "29_29") (pintype "passive"))
      (node (ref "U$28") (pin "P$3") (pinfunction "C_P$3") (pintype "passive"))
    )
    (net (code "193") (name "Net-(U$29-B)") (class "Default")
      (node (ref "R66") (pin "2") (pinfunction "2_2") (pintype "passive"))
      (node (ref "U$29") (pin "P$1") (pinfunction "B_P$1") (pintype "passive"))
    )
    (net (code "194") (name "Net-(U$29-C)") (class "Default")
      (node (ref "SV1") (pin "26") (pinfunction "26_26") (pintype "passive"))
      (node (ref "U$29") (pin "P$3") (pinfunction "C_P$3") (pintype "passive"))
    )
    (net (code "195") (name "Net-(U$30-B)") (class "Default")
      (node (ref "R67") (pin "2") (pinfunction "2_2") (pintype "passive"))
      (node (ref "U$30") (pin "P$1") (pinfunction "B_P$1") (pintype "passive"))
    )
    (net (code "196") (name "Net-(U$30-C)") (class "Default")
      (node (ref "SV1") (pin "27") (pinfunction "27_27") (pintype "passive"))
      (node (ref "U$30") (pin "P$3") (pinfunction "C_P$3") (pintype "passive"))
    )
    (net (code "197") (name "Net-(U$31-B)") (class "Default")
      (node (ref "R68") (pin "2") (pinfunction "2_2") (pintype "passive"))
      (node (ref "U$31") (pin "P$1") (pinfunction "B_P$1") (pintype "passive"))
    )
    (net (code "198") (name "Net-(U$31-C)") (class "Default")
      (node (ref "SV1") (pin "30") (pinfunction "30_30") (pintype "passive"))
      (node (ref "U$31") (pin "P$3") (pinfunction "C_P$3") (pintype "passive"))
    )
    (net (code "199") (name "Net-(U$32-B)") (class "Default")
      (node (ref "R69") (pin "2") (pinfunction "2_2") (pintype "passive"))
      (node (ref "U$32") (pin "P$1") (pinfunction "B_P$1") (pintype "passive"))
    )
    (net (code "200") (name "Net-(U$32-C)") (class "Default")
      (node (ref "SV1") (pin "31") (pinfunction "31_31") (pintype "passive"))
      (node (ref "U$32") (pin "P$3") (pinfunction "C_P$3") (pintype "passive"))
    )
    (net (code "201") (name "Net-(U$33-B)") (class "Default")
      (node (ref "R70") (pin "2") (pinfunction "2_2") (pintype "passive"))
      (node (ref "U$33") (pin "P$1") (pinfunction "B_P$1") (pintype "passive"))
    )
    (net (code "202") (name "Net-(U$33-C)") (class "Default")
      (node (ref "SV1") (pin "32") (pinfunction "32_32") (pintype "passive"))
      (node (ref "U$33") (pin "P$3") (pinfunction "C_P$3") (pintype "passive"))
    )
    (net (code "203") (name "Net-(U$34-B)") (class "Default")
      (node (ref "R71") (pin "2") (pinfunction "2_2") (pintype "passive"))
      (node (ref "U$34") (pin "P$1") (pinfunction "B_P$1") (pintype "passive"))
    )
    (net (code "204") (name "Net-(U$34-C)") (class "Default")
      (node (ref "SV1") (pin "33") (pinfunction "33_33") (pintype "passive"))
      (node (ref "U$34") (pin "P$3") (pinfunction "C_P$3") (pintype "passive"))
    )
    (net (code "205") (name "Net-(U$35-B)") (class "Default")
      (node (ref "R72") (pin "2") (pinfunction "2_2") (pintype "passive"))
      (node (ref "U$35") (pin "P$1") (pinfunction "B_P$1") (pintype "passive"))
    )
    (net (code "206") (name "Net-(U$35-C)") (class "Default")
      (node (ref "SV1") (pin "36") (pinfunction "36_36") (pintype "passive"))
      (node (ref "U$35") (pin "P$3") (pinfunction "C_P$3") (pintype "passive"))
    )
    (net (code "207") (name "Net-(U$36-B)") (class "Default")
      (node (ref "R73") (pin "2") (pinfunction "2_2") (pintype "passive"))
      (node (ref "U$36") (pin "P$1") (pinfunction "B_P$1") (pintype "passive"))
    )
    (net (code "208") (name "Net-(U$36-C)") (class "Default")
      (node (ref "SV1") (pin "37") (pinfunction "37_37") (pintype "passive"))
      (node (ref "U$36") (pin "P$3") (pinfunction "C_P$3") (pintype "passive"))
    )
    (net (code "209") (name "Net-(U$37-B)") (class "Default")
      (node (ref "R74") (pin "2") (pinfunction "2_2") (pintype "passive"))
      (node (ref "U$37") (pin "P$1") (pinfunction "B_P$1") (pintype "passive"))
    )
    (net (code "210") (name "Net-(U$37-C)") (class "Default")
      (node (ref "SV1") (pin "34") (pinfunction "34_34") (pintype "passive"))
      (node (ref "U$37") (pin "P$3") (pinfunction "C_P$3") (pintype "passive"))
    )
    (net (code "211") (name "Net-(U$38-B)") (class "Default")
      (node (ref "R75") (pin "2") (pinfunction "2_2") (pintype "passive"))
      (node (ref "U$38") (pin "P$1") (pinfunction "B_P$1") (pintype "passive"))
    )
    (net (code "212") (name "Net-(U$38-C)") (class "Default")
      (node (ref "SV1") (pin "35") (pinfunction "35_35") (pintype "passive"))
      (node (ref "U$38") (pin "P$3") (pinfunction "C_P$3") (pintype "passive"))
    )
    (net (code "213") (name "Net-(U$39-B)") (class "Default")
      (node (ref "R76") (pin "2") (pinfunction "2_2") (pintype "passive"))
      (node (ref "U$39") (pin "P$1") (pinfunction "B_P$1") (pintype "passive"))
    )
    (net (code "214") (name "Net-(U$39-C)") (class "Default")
      (node (ref "SV1") (pin "38") (pinfunction "38_38") (pintype "passive"))
      (node (ref "U$39") (pin "P$3") (pinfunction "C_P$3") (pintype "passive"))
    )
    (net (code "215") (name "Net-(U$40-B)") (class "Default")
      (node (ref "R77") (pin "2") (pinfunction "2_2") (pintype "passive"))
      (node (ref "U$40") (pin "P$1") (pinfunction "B_P$1") (pintype "passive"))
    )
    (net (code "216") (name "Net-(U$40-C)") (class "Default")
      (node (ref "SV1") (pin "39") (pinfunction "39_39") (pintype "passive"))
      (node (ref "U$40") (pin "P$3") (pinfunction "C_P$3") (pintype "passive"))
    )
    (net (code "217") (name "Net-(U$41-B)") (class "Default")
      (node (ref "R78") (pin "2") (pinfunction "2_2") (pintype "passive"))
      (node (ref "U$41") (pin "P$1") (pinfunction "B_P$1") (pintype "passive"))
    )
    (net (code "218") (name "Net-(U$41-C)") (class "Default")
      (node (ref "SV1") (pin "40") (pinfunction "40_40") (pintype "passive"))
      (node (ref "U$41") (pin "P$3") (pinfunction "C_P$3") (pintype "passive"))
    )
    (net (code "219") (name "Net-(U$42-B)") (class "Default")
      (node (ref "R79") (pin "2") (pinfunction "2_2") (pintype "passive"))
      (node (ref "U$42") (pin "P$1") (pinfunction "B_P$1") (pintype "passive"))
    )
    (net (code "220") (name "Net-(U$42-C)") (class "Default")
      (node (ref "SV1") (pin "41") (pinfunction "41_41") (pintype "passive"))
      (node (ref "U$42") (pin "P$3") (pinfunction "C_P$3") (pintype "passive"))
    )
    (net (code "221") (name "Net-(U$43-B)") (class "Default")
      (node (ref "R80") (pin "2") (pinfunction "2_2") (pintype "passive"))
      (node (ref "U$43") (pin "P$1") (pinfunction "B_P$1") (pintype "passive"))
    )
    (net (code "222") (name "Net-(U$43-C)") (class "Default")
      (node (ref "SV1") (pin "44") (pinfunction "44_44") (pintype "passive"))
      (node (ref "U$43") (pin "P$3") (pinfunction "C_P$3") (pintype "passive"))
    )
    (net (code "223") (name "Net-(U$44-B)") (class "Default")
      (node (ref "R81") (pin "2") (pinfunction "2_2") (pintype "passive"))
      (node (ref "U$44") (pin "P$1") (pinfunction "B_P$1") (pintype "passive"))
    )
    (net (code "224") (name "Net-(U$44-C)") (class "Default")
      (node (ref "SV1") (pin "45") (pinfunction "45_45") (pintype "passive"))
      (node (ref "U$44") (pin "P$3") (pinfunction "C_P$3") (pintype "passive"))
    )
    (net (code "225") (name "Net-(U$45-B)") (class "Default")
      (node (ref "R82") (pin "2") (pinfunction "2_2") (pintype "passive"))
      (node (ref "U$45") (pin "P$1") (pinfunction "B_P$1") (pintype "passive"))
    )
    (net (code "226") (name "Net-(U$45-C)") (class "Default")
      (node (ref "SV1") (pin "42") (pinfunction "42_42") (pintype "passive"))
      (node (ref "U$45") (pin "P$3") (pinfunction "C_P$3") (pintype "passive"))
    )
    (net (code "227") (name "Net-(U$46-B)") (class "Default")
      (node (ref "R83") (pin "2") (pinfunction "2_2") (pintype "passive"))
      (node (ref "U$46") (pin "P$1") (pinfunction "B_P$1") (pintype "passive"))
    )
    (net (code "228") (name "Net-(U$46-C)") (class "Default")
      (node (ref "SV1") (pin "43") (pinfunction "43_43") (pintype "passive"))
      (node (ref "U$46") (pin "P$3") (pinfunction "C_P$3") (pintype "passive"))
    )
    (net (code "229") (name "Net-(U$47-B)") (class "Default")
      (node (ref "R84") (pin "2") (pinfunction "2_2") (pintype "passive"))
      (node (ref "U$47") (pin "P$1") (pinfunction "B_P$1") (pintype "passive"))
    )
    (net (code "230") (name "Net-(U$47-C)") (class "Default")
      (node (ref "SV1") (pin "46") (pinfunction "46_46") (pintype "passive"))
      (node (ref "U$47") (pin "P$3") (pinfunction "C_P$3") (pintype "passive"))
    )
    (net (code "231") (name "Net-(U$48-B)") (class "Default")
      (node (ref "R85") (pin "2") (pinfunction "2_2") (pintype "passive"))
      (node (ref "U$48") (pin "P$1") (pinfunction "B_P$1") (pintype "passive"))
    )
    (net (code "232") (name "Net-(U$48-C)") (class "Default")
      (node (ref "SV1") (pin "47") (pinfunction "47_47") (pintype "passive"))
      (node (ref "U$48") (pin "P$3") (pinfunction "C_P$3") (pintype "passive"))
    )
    (net (code "233") (name "Net-(U$49-B)") (class "Default")
      (node (ref "R86") (pin "2") (pinfunction "2_2") (pintype "passive"))
      (node (ref "U$49") (pin "P$1") (pinfunction "B_P$1") (pintype "passive"))
    )
    (net (code "234") (name "Net-(U$49-C)") (class "Default")
      (node (ref "SV1") (pin "48") (pinfunction "48_48") (pintype "passive"))
      (node (ref "U$49") (pin "P$3") (pinfunction "C_P$3") (pintype "passive"))
    )
    (net (code "235") (name "Net-(U$50-B)") (class "Default")
      (node (ref "R87") (pin "2") (pinfunction "2_2") (pintype "passive"))
      (node (ref "U$50") (pin "P$1") (pinfunction "B_P$1") (pintype "passive"))
    )
    (net (code "236") (name "Net-(U$50-C)") (class "Default")
      (node (ref "SV1") (pin "49") (pinfunction "49_49") (pintype "passive"))
      (node (ref "U$50") (pin "P$3") (pinfunction "C_P$3") (pintype "passive"))
    )
    (net (code "237") (name "Net-(U$51-B)") (class "Default")
      (node (ref "R88") (pin "2") (pinfunction "2_2") (pintype "passive"))
      (node (ref "U$51") (pin "P$1") (pinfunction "B_P$1") (pintype "passive"))
    )
    (net (code "238") (name "Net-(U$51-C)") (class "Default")
      (node (ref "SV1") (pin "52") (pinfunction "52_52") (pintype "passive"))
      (node (ref "U$51") (pin "P$3") (pinfunction "C_P$3") (pintype "passive"))
    )
    (net (code "239") (name "Net-(U$52-B)") (class "Default")
      (node (ref "R89") (pin "2") (pinfunction "2_2") (pintype "passive"))
      (node (ref "U$52") (pin "P$1") (pinfunction "B_P$1") (pintype "passive"))
    )
    (net (code "240") (name "Net-(U$52-C)") (class "Default")
      (node (ref "SV1") (pin "53") (pinfunction "53_53") (pintype "passive"))
      (node (ref "U$52") (pin "P$3") (pinfunction "C_P$3") (pintype "passive"))
    )
    (net (code "241") (name "Net-(U$53-B)") (class "Default")
      (node (ref "R90") (pin "2") (pinfunction "2_2") (pintype "passive"))
      (node (ref "U$53") (pin "P$1") (pinfunction "B_P$1") (pintype "passive"))
    )
    (net (code "242") (name "Net-(U$53-C)") (class "Default")
      (node (ref "SV1") (pin "50") (pinfunction "50_50") (pintype "passive"))
      (node (ref "U$53") (pin "P$3") (pinfunction "C_P$3") (pintype "passive"))
    )
    (net (code "243") (name "Net-(U$54-B)") (class "Default")
      (node (ref "R91") (pin "2") (pinfunction "2_2") (pintype "passive"))
      (node (ref "U$54") (pin "P$1") (pinfunction "B_P$1") (pintype "passive"))
    )
    (net (code "244") (name "Net-(U$54-C)") (class "Default")
      (node (ref "SV1") (pin "51") (pinfunction "51_51") (pintype "passive"))
      (node (ref "U$54") (pin "P$3") (pinfunction "C_P$3") (pintype "passive"))
    )
    (net (code "245") (name "Net-(U$55-B)") (class "Default")
      (node (ref "R92") (pin "2") (pinfunction "2_2") (pintype "passive"))
      (node (ref "U$55") (pin "P$1") (pinfunction "B_P$1") (pintype "passive"))
    )
    (net (code "246") (name "Net-(U$55-C)") (class "Default")
      (node (ref "SV1") (pin "54") (pinfunction "54_54") (pintype "passive"))
      (node (ref "U$55") (pin "P$3") (pinfunction "C_P$3") (pintype "passive"))
    )
    (net (code "247") (name "Net-(U$56-B)") (class "Default")
      (node (ref "R93") (pin "2") (pinfunction "2_2") (pintype "passive"))
      (node (ref "U$56") (pin "P$1") (pinfunction "B_P$1") (pintype "passive"))
    )
    (net (code "248") (name "Net-(U$56-C)") (class "Default")
      (node (ref "SV1") (pin "55") (pinfunction "55_55") (pintype "passive"))
      (node (ref "U$56") (pin "P$3") (pinfunction "C_P$3") (pintype "passive"))
    )
    (net (code "249") (name "Net-(U$57-B)") (class "Default")
      (node (ref "R94") (pin "2") (pinfunction "2_2") (pintype "passive"))
      (node (ref "U$57") (pin "P$1") (pinfunction "B_P$1") (pintype "passive"))
    )
    (net (code "250") (name "Net-(U$57-C)") (class "Default")
      (node (ref "SV1") (pin "56") (pinfunction "56_56") (pintype "passive"))
      (node (ref "U$57") (pin "P$3") (pinfunction "C_P$3") (pintype "passive"))
    )
    (net (code "251") (name "Net-(U$58-B)") (class "Default")
      (node (ref "R95") (pin "2") (pinfunction "2_2") (pintype "passive"))
      (node (ref "U$58") (pin "P$1") (pinfunction "B_P$1") (pintype "passive"))
    )
    (net (code "252") (name "Net-(U$58-C)") (class "Default")
      (node (ref "SV1") (pin "57") (pinfunction "57_57") (pintype "passive"))
      (node (ref "U$58") (pin "P$3") (pinfunction "C_P$3") (pintype "passive"))
    )
    (net (code "253") (name "Net-(U$59-B)") (class "Default")
      (node (ref "R96") (pin "2") (pinfunction "2_2") (pintype "passive"))
      (node (ref "U$59") (pin "P$1") (pinfunction "B_P$1") (pintype "passive"))
    )
    (net (code "254") (name "Net-(U$59-C)") (class "Default")
      (node (ref "SV1") (pin "60") (pinfunction "60_60") (pintype "passive"))
      (node (ref "U$59") (pin "P$3") (pinfunction "C_P$3") (pintype "passive"))
    )
    (net (code "255") (name "Net-(U$60-B)") (class "Default")
      (node (ref "R97") (pin "2") (pinfunction "2_2") (pintype "passive"))
      (node (ref "U$60") (pin "P$1") (pinfunction "B_P$1") (pintype "passive"))
    )
    (net (code "256") (name "Net-(U$60-C)") (class "Default")
      (node (ref "SV1") (pin "61") (pinfunction "61_61") (pintype "passive"))
      (node (ref "U$60") (pin "P$3") (pinfunction "C_P$3") (pintype "passive"))
    )
    (net (code "257") (name "Net-(U$61-B)") (class "Default")
      (node (ref "R98") (pin "2") (pinfunction "2_2") (pintype "passive"))
      (node (ref "U$61") (pin "P$1") (pinfunction "B_P$1") (pintype "passive"))
    )
    (net (code "258") (name "Net-(U$61-C)") (class "Default")
      (node (ref "SV1") (pin "58") (pinfunction "58_58") (pintype "passive"))
      (node (ref "U$61") (pin "P$3") (pinfunction "C_P$3") (pintype "passive"))
    )
    (net (code "259") (name "Net-(U$62-B)") (class "Default")
      (node (ref "R99") (pin "2") (pinfunction "2_2") (pintype "passive"))
      (node (ref "U$62") (pin "P$1") (pinfunction "B_P$1") (pintype "passive"))
    )
    (net (code "260") (name "Net-(U$62-C)") (class "Default")
      (node (ref "SV1") (pin "59") (pinfunction "59_59") (pintype "passive"))
      (node (ref "U$62") (pin "P$3") (pinfunction "C_P$3") (pintype "passive"))
    )
    (net (code "261") (name "Net-(U$63-B)") (class "Default")
      (node (ref "R100") (pin "2") (pinfunction "2_2") (pintype "passive"))
      (node (ref "U$63") (pin "P$1") (pinfunction "B_P$1") (pintype "passive"))
    )
    (net (code "262") (name "Net-(U$63-C)") (class "Default")
      (node (ref "SV1") (pin "62") (pinfunction "62_62") (pintype "passive"))
      (node (ref "U$63") (pin "P$3") (pinfunction "C_P$3") (pintype "passive"))
    )
    (net (code "263") (name "Net-(U$64-B)") (class "Default")
      (node (ref "R101") (pin "2") (pinfunction "2_2") (pintype "passive"))
      (node (ref "U$64") (pin "P$1") (pinfunction "B_P$1") (pintype "passive"))
    )
    (net (code "264") (name "Net-(U$64-C)") (class "Default")
      (node (ref "SV1") (pin "63") (pinfunction "63_63") (pintype "passive"))
      (node (ref "U$64") (pin "P$3") (pinfunction "C_P$3") (pintype "passive"))
    )
    (net (code "265") (name "Net-(U$65-B)") (class "Default")
      (node (ref "R102") (pin "2") (pinfunction "2_2") (pintype "passive"))
      (node (ref "U$65") (pin "P$1") (pinfunction "B_P$1") (pintype "passive"))
    )
    (net (code "266") (name "Net-(U$65-C)") (class "Default")
      (node (ref "SV1") (pin "64") (pinfunction "64_64") (pintype "passive"))
      (node (ref "U$65") (pin "P$3") (pinfunction "C_P$3") (pintype "passive"))
    )
    (net (code "267") (name "Net-(U$66-G)") (class "Default")
      (node (ref "R2") (pin "2") (pinfunction "2_2") (pintype "passive"))
      (node (ref "R23") (pin "1") (pinfunction "1_1") (pintype "passive"))
      (node (ref "U$66") (pin "1") (pinfunction "G_1") (pintype "passive"))
    )
    (net (code "268") (name "Net-(U$67-G)") (class "Default")
      (node (ref "R24") (pin "1") (pinfunction "1_1") (pintype "passive"))
      (node (ref "R3") (pin "2") (pinfunction "2_2") (pintype "passive"))
      (node (ref "U$67") (pin "1") (pinfunction "G_1") (pintype "passive"))
    )
    (net (code "269") (name "Net-(U$68-G)") (class "Default")
      (node (ref "R25") (pin "1") (pinfunction "1_1") (pintype "passive"))
      (node (ref "R4") (pin "2") (pinfunction "2_2") (pintype "passive"))
      (node (ref "U$68") (pin "1") (pinfunction "G_1") (pintype "passive"))
    )
    (net (code "270") (name "Net-(U$69-G)") (class "Default")
      (node (ref "R26") (pin "1") (pinfunction "1_1") (pintype "passive"))
      (node (ref "R5") (pin "2") (pinfunction "2_2") (pintype "passive"))
      (node (ref "U$69") (pin "1") (pinfunction "G_1") (pintype "passive"))
    )
    (net (code "271") (name "Net-(U$70-G)") (class "Default")
      (node (ref "R27") (pin "1") (pinfunction "1_1") (pintype "passive"))
      (node (ref "R6") (pin "2") (pinfunction "2_2") (pintype "passive"))
      (node (ref "U$70") (pin "1") (pinfunction "G_1") (pintype "passive"))
    )
    (net (code "272") (name "Net-(U$71-G)") (class "Default")
      (node (ref "R28") (pin "1") (pinfunction "1_1") (pintype "passive"))
      (node (ref "R7") (pin "2") (pinfunction "2_2") (pintype "passive"))
      (node (ref "U$71") (pin "1") (pinfunction "G_1") (pintype "passive"))
    )
    (net (code "273") (name "Net-(U$72-G)") (class "Default")
      (node (ref "R29") (pin "1") (pinfunction "1_1") (pintype "passive"))
      (node (ref "R8") (pin "2") (pinfunction "2_2") (pintype "passive"))
      (node (ref "U$72") (pin "1") (pinfunction "G_1") (pintype "passive"))
    )
    (net (code "274") (name "Net-(U$73-G)") (class "Default")
      (node (ref "R30") (pin "1") (pinfunction "1_1") (pintype "passive"))
      (node (ref "R9") (pin "2") (pinfunction "2_2") (pintype "passive"))
      (node (ref "U$73") (pin "1") (pinfunction "G_1") (pintype "passive"))
    )
    (net (code "275") (name "VCC") (class "Default")
      (node (ref "C1") (pin "2") (pinfunction "2_2") (pintype "passive"))
      (node (ref "C10") (pin "2") (pinfunction "2_2") (pintype "passive"))
      (node (ref "C16") (pin "1") (pinfunction "1_1") (pintype "passive"))
      (node (ref "C17") (pin "1") (pinfunction "1_1") (pintype "passive"))
      (node (ref "C22") (pin "2") (pinfunction "2_2") (pintype "passive"))
      (node (ref "C23") (pin "2") (pinfunction "2_2") (pintype "passive"))
      (node (ref "C24") (pin "2") (pinfunction "2_2") (pintype "passive"))
      (node (ref "C25") (pin "2") (pinfunction "2_2") (pintype "passive"))
      (node (ref "C26") (pin "2") (pinfunction "2_2") (pintype "passive"))
      (node (ref "C27") (pin "2") (pinfunction "2_2") (pintype "passive"))
      (node (ref "C28") (pin "2") (pinfunction "2_2") (pintype "passive"))
      (node (ref "C29") (pin "2") (pinfunction "2_2") (pintype "passive"))
      (node (ref "C3") (pin "1") (pinfunction "1_1") (pintype "passive"))
      (node (ref "C30") (pin "2") (pinfunction "2_2") (pintype "passive"))
      (node (ref "C7") (pin "2") (pinfunction "2_2") (pintype "passive"))
      (node (ref "C8") (pin "2") (pinfunction "2_2") (pintype "passive"))
      (node (ref "C9") (pin "2") (pinfunction "2_2") (pintype "passive"))
      (node (ref "IC1") (pin "18") (pinfunction "AVCC_18") (pintype "power_in"))
      (node (ref "IC1") (pin "4") (pinfunction "VCC_4") (pintype "power_in"))
      (node (ref "IC1") (pin "6") (pinfunction "VCC_6") (pintype "power_in"))
      (node (ref "IC10") (pin "20") (pinfunction "VCC_20") (pintype "power_in"))
      (node (ref "IC10") (pin "4") (pinfunction "VCCIO_4") (pintype "power_in"))
      (node (ref "IC11") (pin "PH") (pinfunction "VCC_PH") (pintype "power_in"))
      (node (ref "IC12") (pin "1") (pinfunction "VDDA_1") (pintype "power_in"))
      (node (ref "IC14") (pin "17") (pinfunction "VCC1_17") (pintype "power_in"))
      (node (ref "IC14") (pin "27") (pinfunction "AVCC_27") (pintype "power_in"))
      (node (ref "IC14") (pin "38") (pinfunction "VCC2_38") (pintype "power_in"))
      (node (ref "IC14") (pin "5") (pinfunction "VCC_5") (pintype "power_in"))
      (node (ref "JP1") (pin "10") (pinfunction "VCC_10") (pintype "power_in"))
      (node (ref "JP2") (pin "2") (pinfunction "2_2") (pintype "passive"))
      (node (ref "JP3") (pin "2") (pinfunction "+5V_2") (pintype "power_in"))
      (node (ref "JP6") (pin "2") (pinfunction "+5V_2") (pintype "power_in"))
      (node (ref "R1") (pin "1") (pinfunction "1_1") (pintype "passive"))
      (node (ref "R12") (pin "2") (pinfunction "2_2") (pintype "passive"))
      (node (ref "R13") (pin "2") (pinfunction "2_2") (pintype "passive"))
      (node (ref "R15") (pin "1") (pinfunction "1_1") (pintype "passive"))
      (node (ref "R18") (pin "A") (pinfunction "A_A") (pintype "passive"))
      (node (ref "R19") (pin "2") (pinfunction "2_2") (pintype "passive"))
      (node (ref "R20") (pin "1") (pinfunction "1_1") (pintype "passive"))
      (node (ref "U$10") (pin "P$2") (pinfunction "E_P$2") (pintype "passive"))
      (node (ref "U$11") (pin "P$2") (pinfunction "E_P$2") (pintype "passive"))
      (node (ref "U$12") (pin "P$2") (pinfunction "E_P$2") (pintype "passive"))
      (node (ref "U$13") (pin "P$2") (pinfunction "E_P$2") (pintype "passive"))
      (node (ref "U$14") (pin "P$2") (pinfunction "E_P$2") (pintype "passive"))
      (node (ref "U$15") (pin "P$2") (pinfunction "E_P$2") (pintype "passive"))
      (node (ref "U$16") (pin "P$2") (pinfunction "E_P$2") (pintype "passive"))
      (node (ref "U$17") (pin "P$2") (pinfunction "E_P$2") (pintype "passive"))
      (node (ref "U$18") (pin "P$2") (pinfunction "E_P$2") (pintype "passive"))
      (node (ref "U$19") (pin "P$2") (pinfunction "E_P$2") (pintype "passive"))
      (node (ref "U$2") (pin "P$2") (pinfunction "E_P$2") (pintype "passive"))
      (node (ref "U$20") (pin "P$2") (pinfunction "E_P$2") (pintype "passive"))
      (node (ref "U$21") (pin "P$2") (pinfunction "E_P$2") (pintype "passive"))
      (node (ref "U$22") (pin "P$2") (pinfunction "E_P$2") (pintype "passive"))
      (node (ref "U$23") (pin "P$2") (pinfunction "E_P$2") (pintype "passive"))
      (node (ref "U$24") (pin "P$2") (pinfunction "E_P$2") (pintype "passive"))
      (node (ref "U$25") (pin "P$2") (pinfunction "E_P$2") (pintype "passive"))
      (node (ref "U$26") (pin "P$2") (pinfunction "E_P$2") (pintype "passive"))
      (node (ref "U$27") (pin "P$2") (pinfunction "E_P$2") (pintype "passive"))
      (node (ref "U$28") (pin "P$2") (pinfunction "E_P$2") (pintype "passive"))
      (node (ref "U$29") (pin "P$2") (pinfunction "E_P$2") (pintype "passive"))
      (node (ref "U$3") (pin "P$2") (pinfunction "E_P$2") (pintype "passive"))
      (node (ref "U$30") (pin "P$2") (pinfunction "E_P$2") (pintype "passive"))
      (node (ref "U$31") (pin "P$2") (pinfunction "E_P$2") (pintype "passive"))
      (node (ref "U$32") (pin "P$2") (pinfunction "E_P$2") (pintype "passive"))
      (node (ref "U$33") (pin "P$2") (pinfunction "E_P$2") (pintype "passive"))
      (node (ref "U$34") (pin "P$2") (pinfunction "E_P$2") (pintype "passive"))
      (node (ref "U$35") (pin "P$2") (pinfunction "E_P$2") (pintype "passive"))
      (node (ref "U$36") (pin "P$2") (pinfunction "E_P$2") (pintype "passive"))
      (node (ref "U$37") (pin "P$2") (pinfunction "E_P$2") (pintype "passive"))
      (node (ref "U$38") (pin "P$2") (pinfunction "E_P$2") (pintype "passive"))
      (node (ref "U$39") (pin "P$2") (pinfunction "E_P$2") (pintype "passive"))
      (node (ref "U$4") (pin "P$2") (pinfunction "E_P$2") (pintype "passive"))
      (node (ref "U$40") (pin "P$2") (pinfunction "E_P$2") (pintype "passive"))
      (node (ref "U$41") (pin "P$2") (pinfunction "E_P$2") (pintype "passive"))
      (node (ref "U$42") (pin "P$2") (pinfunction "E_P$2") (pintype "passive"))
      (node (ref "U$43") (pin "P$2") (pinfunction "E_P$2") (pintype "passive"))
      (node (ref "U$44") (pin "P$2") (pinfunction "E_P$2") (pintype "passive"))
      (node (ref "U$45") (pin "P$2") (pinfunction "E_P$2") (pintype "passive"))
      (node (ref "U$46") (pin "P$2") (pinfunction "E_P$2") (pintype "passive"))
      (node (ref "U$47") (pin "P$2") (pinfunction "E_P$2") (pintype "passive"))
      (node (ref "U$48") (pin "P$2") (pinfunction "E_P$2") (pintype "passive"))
      (node (ref "U$49") (pin "P$2") (pinfunction "E_P$2") (pintype "passive"))
      (node (ref "U$5") (pin "P$2") (pinfunction "E_P$2") (pintype "passive"))
      (node (ref "U$50") (pin "P$2") (pinfunction "E_P$2") (pintype "passive"))
      (node (ref "U$51") (pin "P$2") (pinfunction "E_P$2") (pintype "passive"))
      (node (ref "U$52") (pin "P$2") (pinfunction "E_P$2") (pintype "passive"))
      (node (ref "U$53") (pin "P$2") (pinfunction "E_P$2") (pintype "passive"))
      (node (ref "U$54") (pin "P$2") (pinfunction "E_P$2") (pintype "passive"))
      (node (ref "U$55") (pin "P$2") (pinfunction "E_P$2") (pintype "passive"))
      (node (ref "U$56") (pin "P$2") (pinfunction "E_P$2") (pintype "passive"))
      (node (ref "U$57") (pin "P$2") (pinfunction "E_P$2") (pintype "passive"))
      (node (ref "U$58") (pin "P$2") (pinfunction "E_P$2") (pintype "passive"))
      (node (ref "U$59") (pin "P$2") (pinfunction "E_P$2") (pintype "passive"))
      (node (ref "U$6") (pin "P$2") (pinfunction "E_P$2") (pintype "passive"))
      (node (ref "U$60") (pin "P$2") (pinfunction "E_P$2") (pintype "passive"))
      (node (ref "U$61") (pin "P$2") (pinfunction "E_P$2") (pintype "passive"))
      (node (ref "U$62") (pin "P$2") (pinfunction "E_P$2") (pintype "passive"))
      (node (ref "U$63") (pin "P$2") (pinfunction "E_P$2") (pintype "passive"))
      (node (ref "U$64") (pin "P$2") (pinfunction "E_P$2") (pintype "passive"))
      (node (ref "U$65") (pin "P$2") (pinfunction "E_P$2") (pintype "passive"))
      (node (ref "U$7") (pin "P$2") (pinfunction "E_P$2") (pintype "passive"))
      (node (ref "U$8") (pin "P$2") (pinfunction "E_P$2") (pintype "passive"))
      (node (ref "U$9") (pin "P$2") (pinfunction "E_P$2") (pintype "passive"))
    )
    (net (code "276") (name "unconnected-(IC1-ADC6-Pad19)") (class "Default")
      (node (ref "IC1") (pin "19") (pinfunction "ADC6_19") (pintype "bidirectional"))
    )
    (net (code "277") (name "unconnected-(IC1-ADC7-Pad22)") (class "Default")
      (node (ref "IC1") (pin "22") (pinfunction "ADC7_22") (pintype "bidirectional"))
    )
    (net (code "278") (name "unconnected-(IC1-PB0(ICP)-Pad12)") (class "Default")
      (node (ref "IC1") (pin "12") (pinfunction "PB0(ICP)_12") (pintype "bidirectional"))
    )
    (net (code "279") (name "unconnected-(IC1-PD0(RXD)-Pad30)") (class "Default")
      (node (ref "IC1") (pin "30") (pinfunction "PD0(RXD)_30") (pintype "bidirectional"))
    )
    (net (code "280") (name "unconnected-(IC1-PD1(TXD)-Pad31)") (class "Default")
      (node (ref "IC1") (pin "31") (pinfunction "PD1(TXD)_31") (pintype "bidirectional"))
    )
    (net (code "281") (name "unconnected-(IC1-PD2(INT0)-Pad32)") (class "Default")
      (node (ref "IC1") (pin "32") (pinfunction "PD2(INT0)_32") (pintype "bidirectional"))
    )
    (net (code "282") (name "unconnected-(IC1-PD3(INT1)-Pad1)") (class "Default")
      (node (ref "IC1") (pin "1") (pinfunction "PD3(INT1)_1") (pintype "bidirectional"))
    )
    (net (code "283") (name "unconnected-(IC1-PD4(XCK{slash}T0)-Pad2)") (class "Default")
      (node (ref "IC1") (pin "2") (pinfunction "PD4(XCK/T0)_2") (pintype "bidirectional"))
    )
    (net (code "284") (name "unconnected-(IC1-PD5(T1)-Pad9)") (class "Default")
      (node (ref "IC1") (pin "9") (pinfunction "PD5(T1)_9") (pintype "bidirectional"))
    )
    (net (code "285") (name "unconnected-(IC1-PD6(AIN0)-Pad10)") (class "Default")
      (node (ref "IC1") (pin "10") (pinfunction "PD6(AIN0)_10") (pintype "bidirectional"))
    )
    (net (code "286") (name "unconnected-(IC1-PD7(AIN1)-Pad11)") (class "Default")
      (node (ref "IC1") (pin "11") (pinfunction "PD7(AIN1)_11") (pintype "bidirectional"))
    )
    (net (code "287") (name "unconnected-(IC10-CBUS0-Pad23)") (class "Default")
      (node (ref "IC10") (pin "23") (pinfunction "CBUS0_23") (pintype "bidirectional"))
    )
    (net (code "288") (name "unconnected-(IC10-CBUS1-Pad22)") (class "Default")
      (node (ref "IC10") (pin "22") (pinfunction "CBUS1_22") (pintype "bidirectional"))
    )
    (net (code "289") (name "unconnected-(IC10-CBUS2-Pad13)") (class "Default")
      (node (ref "IC10") (pin "13") (pinfunction "CBUS2_13") (pintype "bidirectional"))
    )
    (net (code "290") (name "unconnected-(IC10-CBUS3-Pad14)") (class "Default")
      (node (ref "IC10") (pin "14") (pinfunction "CBUS3_14") (pintype "bidirectional"))
    )
    (net (code "291") (name "unconnected-(IC10-CBUS4-Pad12)") (class "Default")
      (node (ref "IC10") (pin "12") (pinfunction "CBUS4_12") (pintype "bidirectional"))
    )
    (net (code "292") (name "unconnected-(IC10-OSCI-Pad27)") (class "Default")
      (node (ref "IC10") (pin "27") (pinfunction "OSCI_27") (pintype "input"))
    )
    (net (code "293") (name "unconnected-(IC10-OSCO-Pad28)") (class "Default")
      (node (ref "IC10") (pin "28") (pinfunction "OSCO_28") (pintype "output"))
    )
    (net (code "294") (name "unconnected-(IC10-~{CTS}-Pad11)") (class "Default")
      (node (ref "IC10") (pin "11") (pinfunction "~{CTS}_11") (pintype "input"))
    )
    (net (code "295") (name "unconnected-(IC10-~{DCD}-Pad10)") (class "Default")
      (node (ref "IC10") (pin "10") (pinfunction "~{DCD}_10") (pintype "input"))
    )
    (net (code "296") (name "unconnected-(IC10-~{DSR}-Pad9)") (class "Default")
      (node (ref "IC10") (pin "9") (pinfunction "~{DSR}_9") (pintype "input"))
    )
    (net (code "297") (name "unconnected-(IC10-~{DTR}-Pad2)") (class "Default")
      (node (ref "IC10") (pin "2") (pinfunction "~{DTR}_2") (pintype "output"))
    )
    (net (code "298") (name "unconnected-(IC10-~{RI}-Pad6)") (class "Default")
      (node (ref "IC10") (pin "6") (pinfunction "~{RI}_6") (pintype "input"))
    )
    (net (code "299") (name "unconnected-(IC10-~{RTS}-Pad3)") (class "Default")
      (node (ref "IC10") (pin "3") (pinfunction "~{RTS}_3") (pintype "output"))
    )
    (net (code "300") (name "unconnected-(JP3-LED-Pad3)") (class "Default")
      (node (ref "JP3") (pin "3") (pinfunction "LED_3") (pintype "output"))
    )
    (net (code "301") (name "unconnected-(JP6-LED-Pad3)") (class "Default")
      (node (ref "JP6") (pin "3") (pinfunction "LED_3") (pintype "output"))
    )
    (net (code "302") (name "unconnected-(U$1-CL-PadCONLEFT)") (class "Default")
      (node (ref "U$1") (pin "CONLEFT") (pinfunction "CL_CONLEFT") (pintype "bidirectional"))
    )
    (net (code "303") (name "unconnected-(U$1-CR-PadCONRIGHT)") (class "Default")
      (node (ref "U$1") (pin "CONRIGHT") (pinfunction "CR_CONRIGHT") (pintype "bidirectional"))
    )
    (net (code "304") (name "unconnected-(X1-Pad3)") (class "Default")
      (node (ref "X1") (pin "3") (pinfunction "3_3") (pintype "passive"))
    )
    (net (code "305") (name "unconnected-(X2-Pad4)") (class "Default")
      (node (ref "X2") (pin "4") (pinfunction "4_4") (pintype "input"))
    )
  )
)
